# TK90X.net
KiCad netlist of a schematic drawn in EAGLE
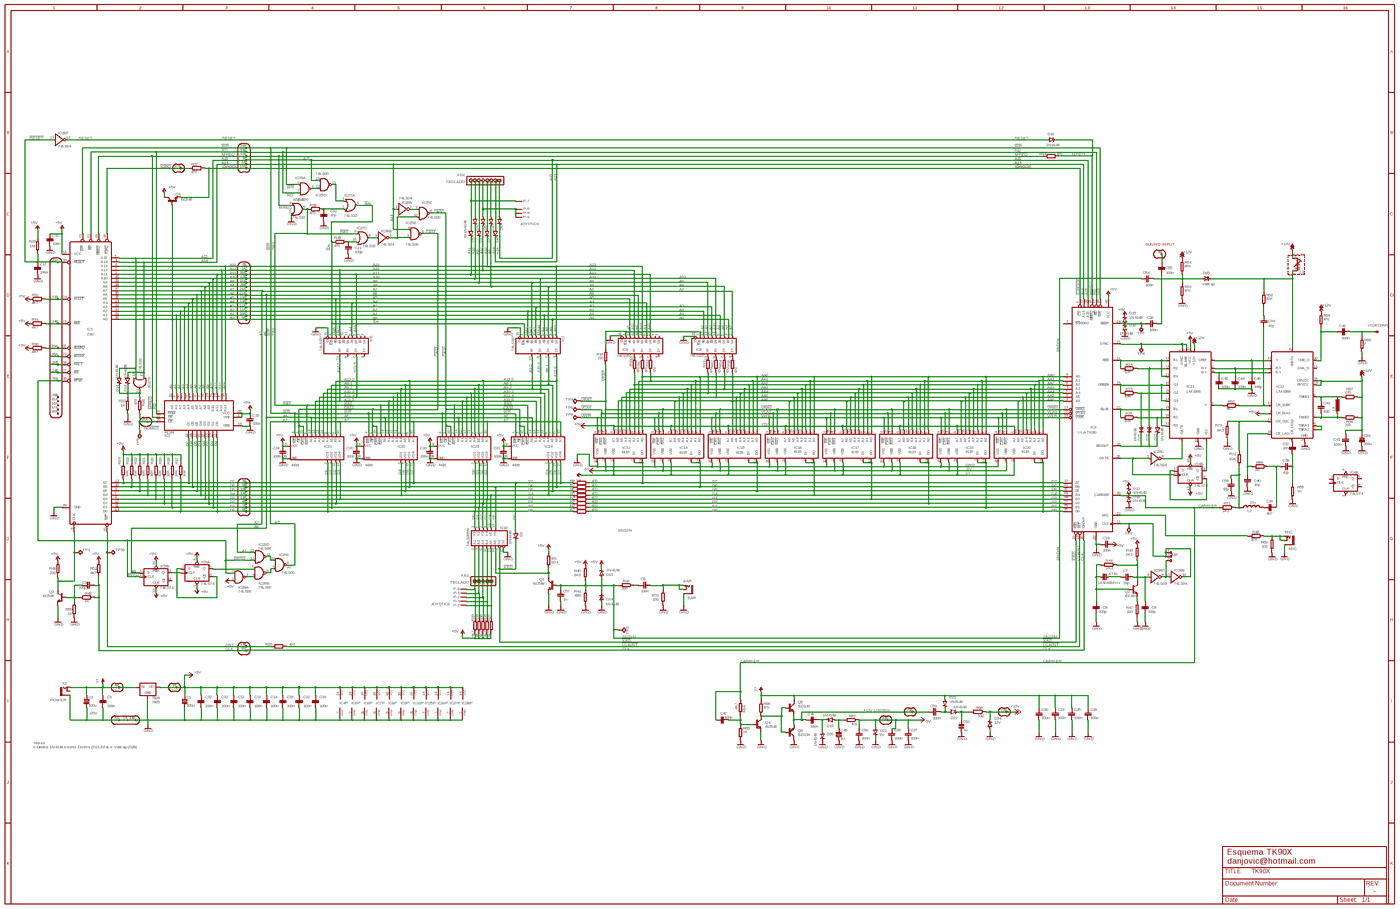
[diagram p0: schematic, sheet 1, overview]
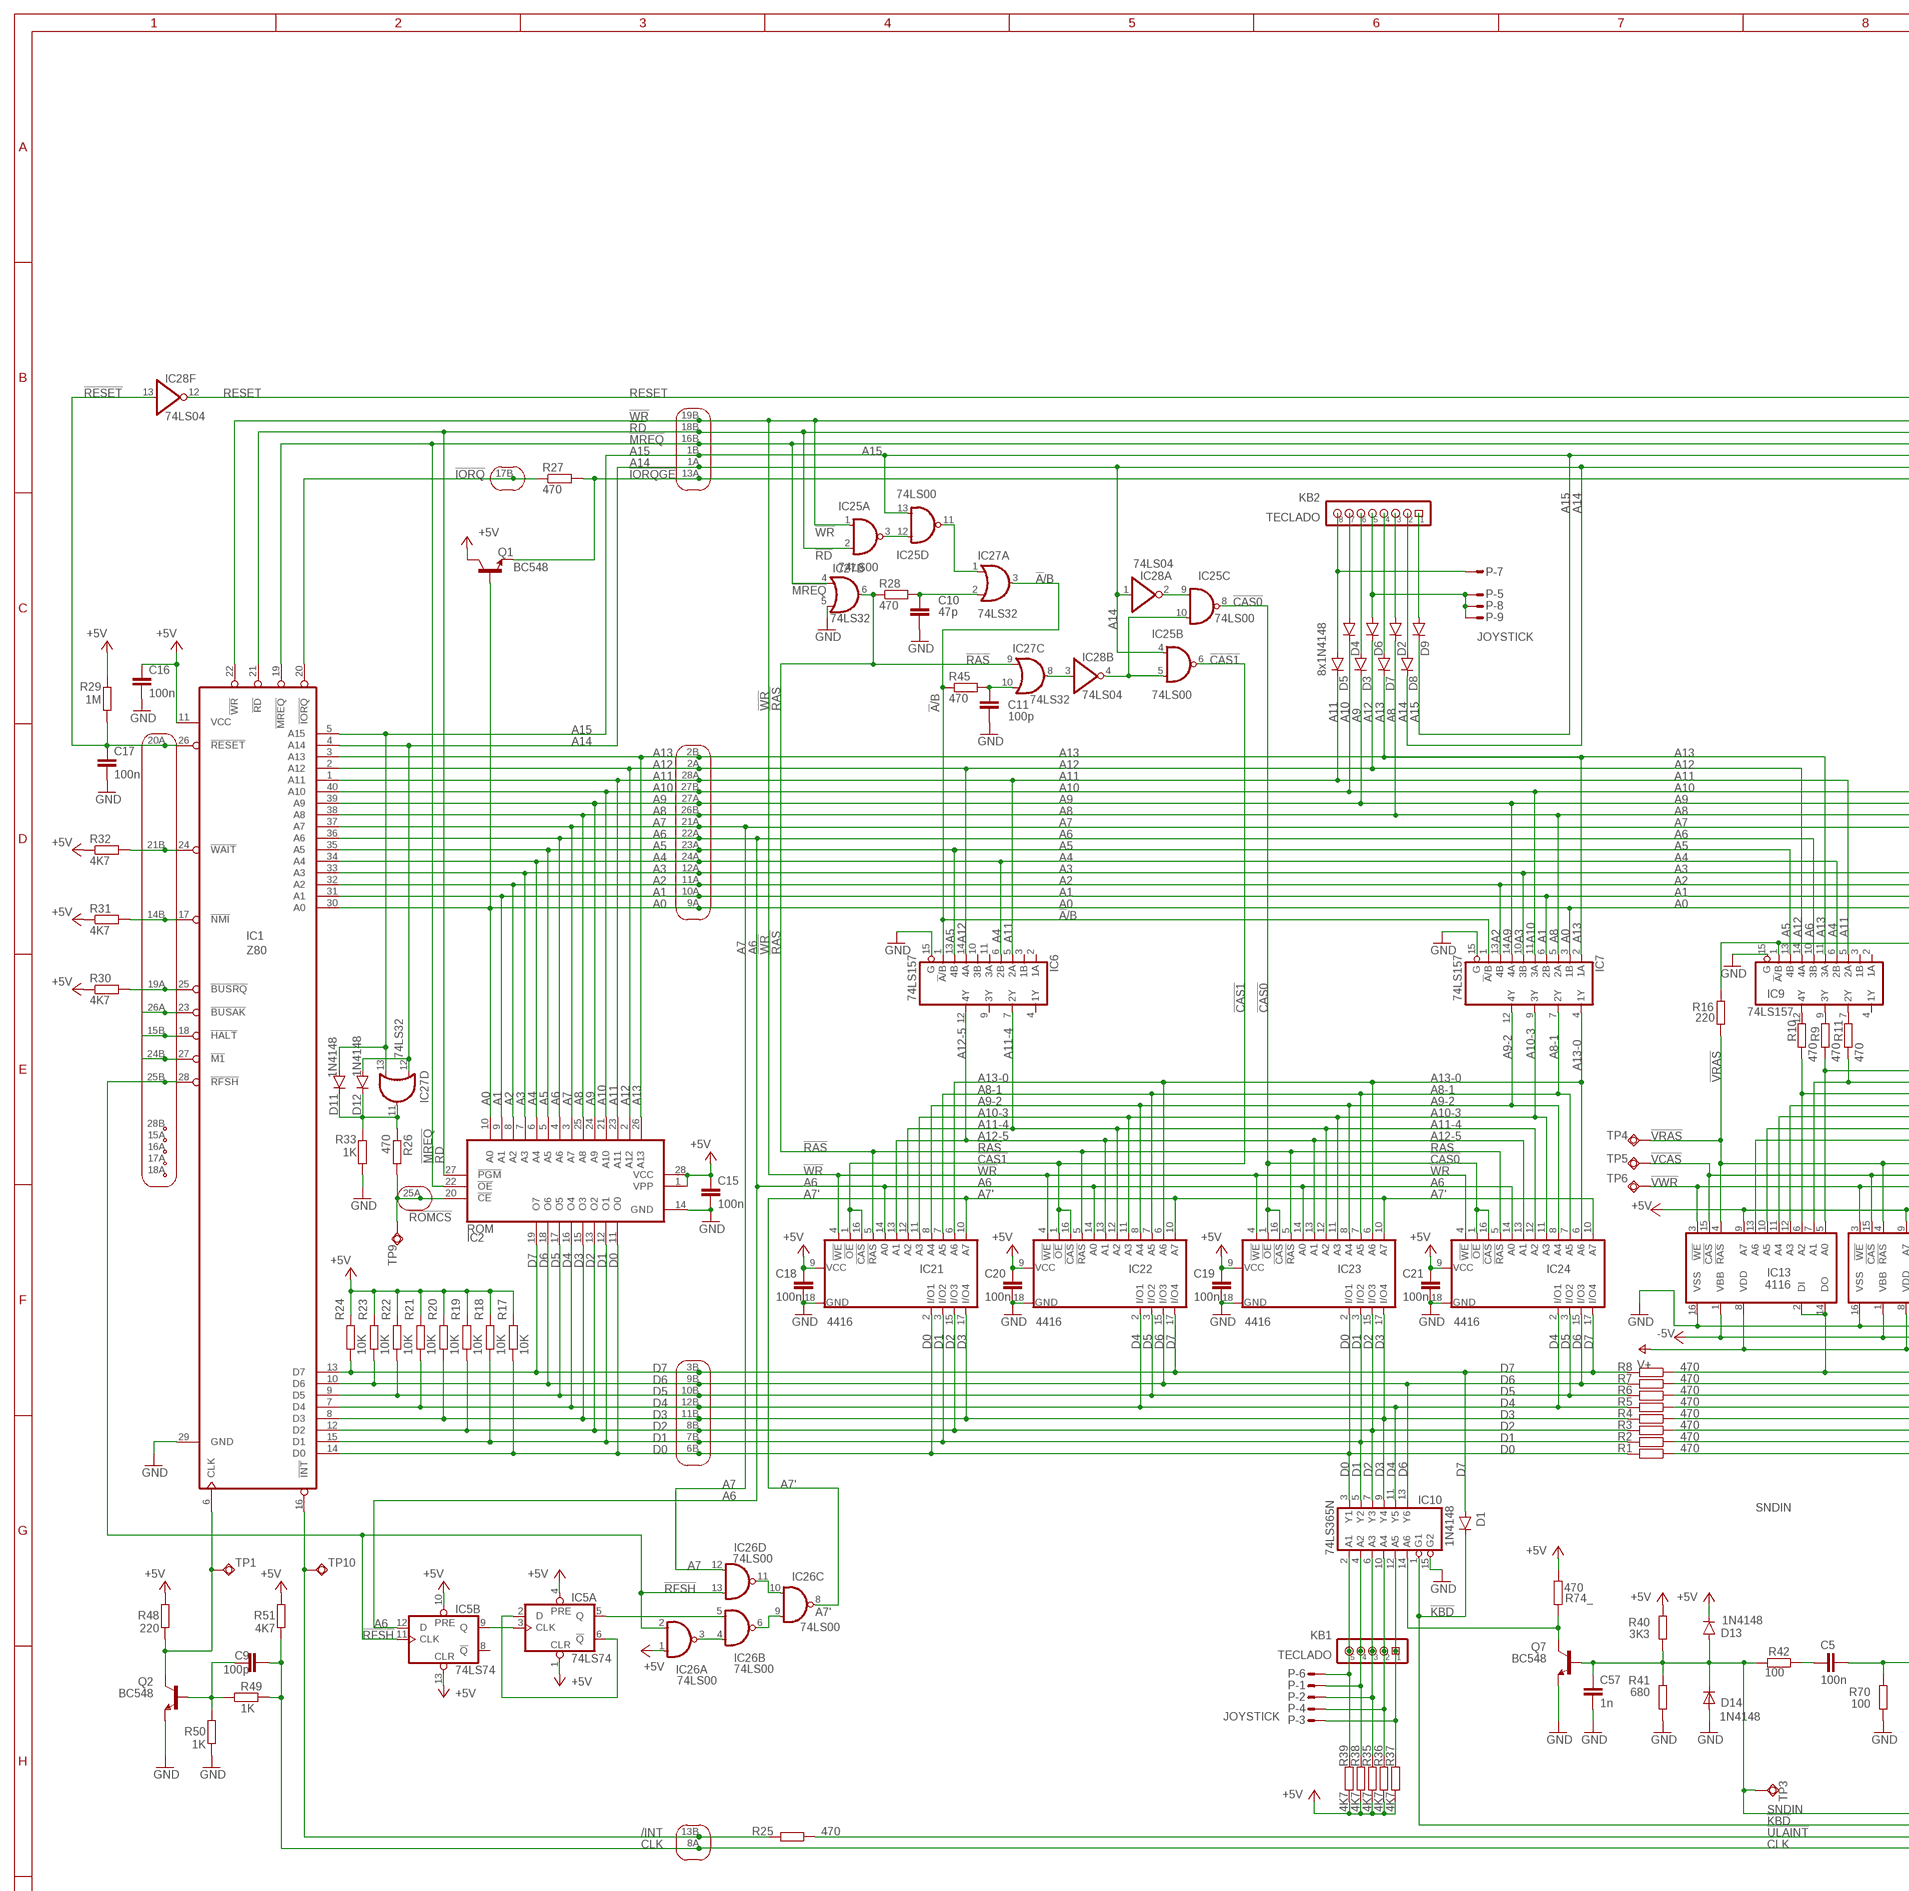
[diagram p1: schematic, sheet 1, part 1 of 4]
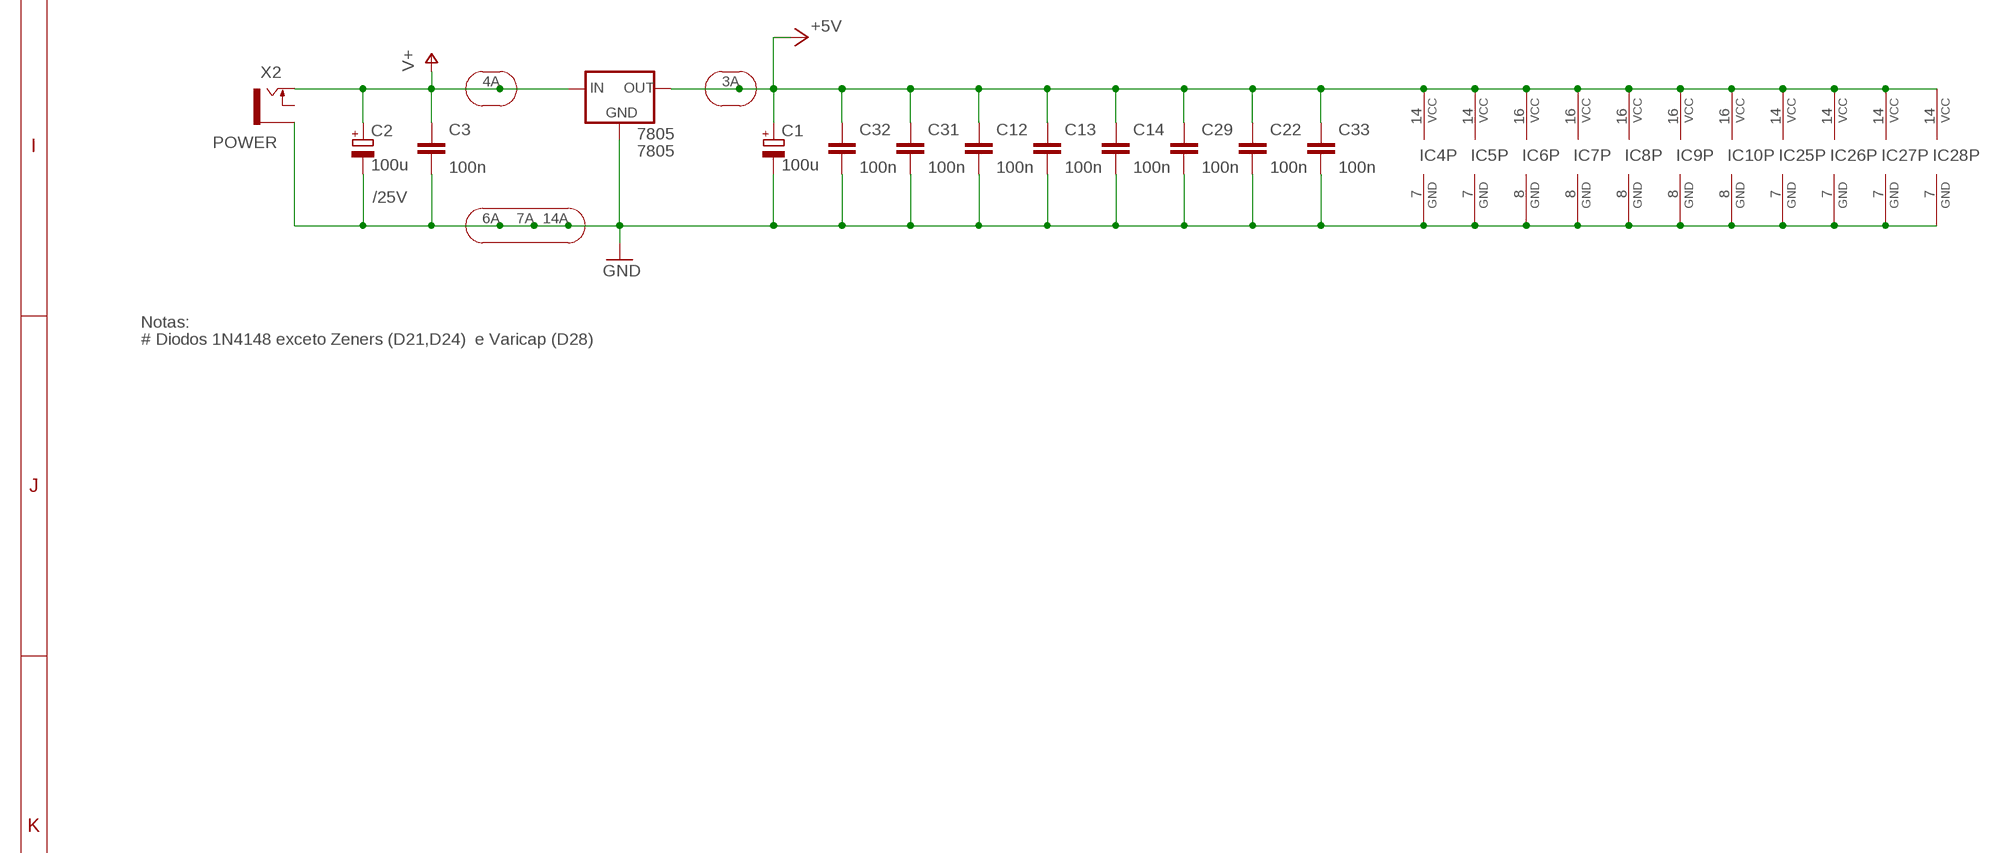
[diagram p2: schematic, sheet 1, part 2 of 4]
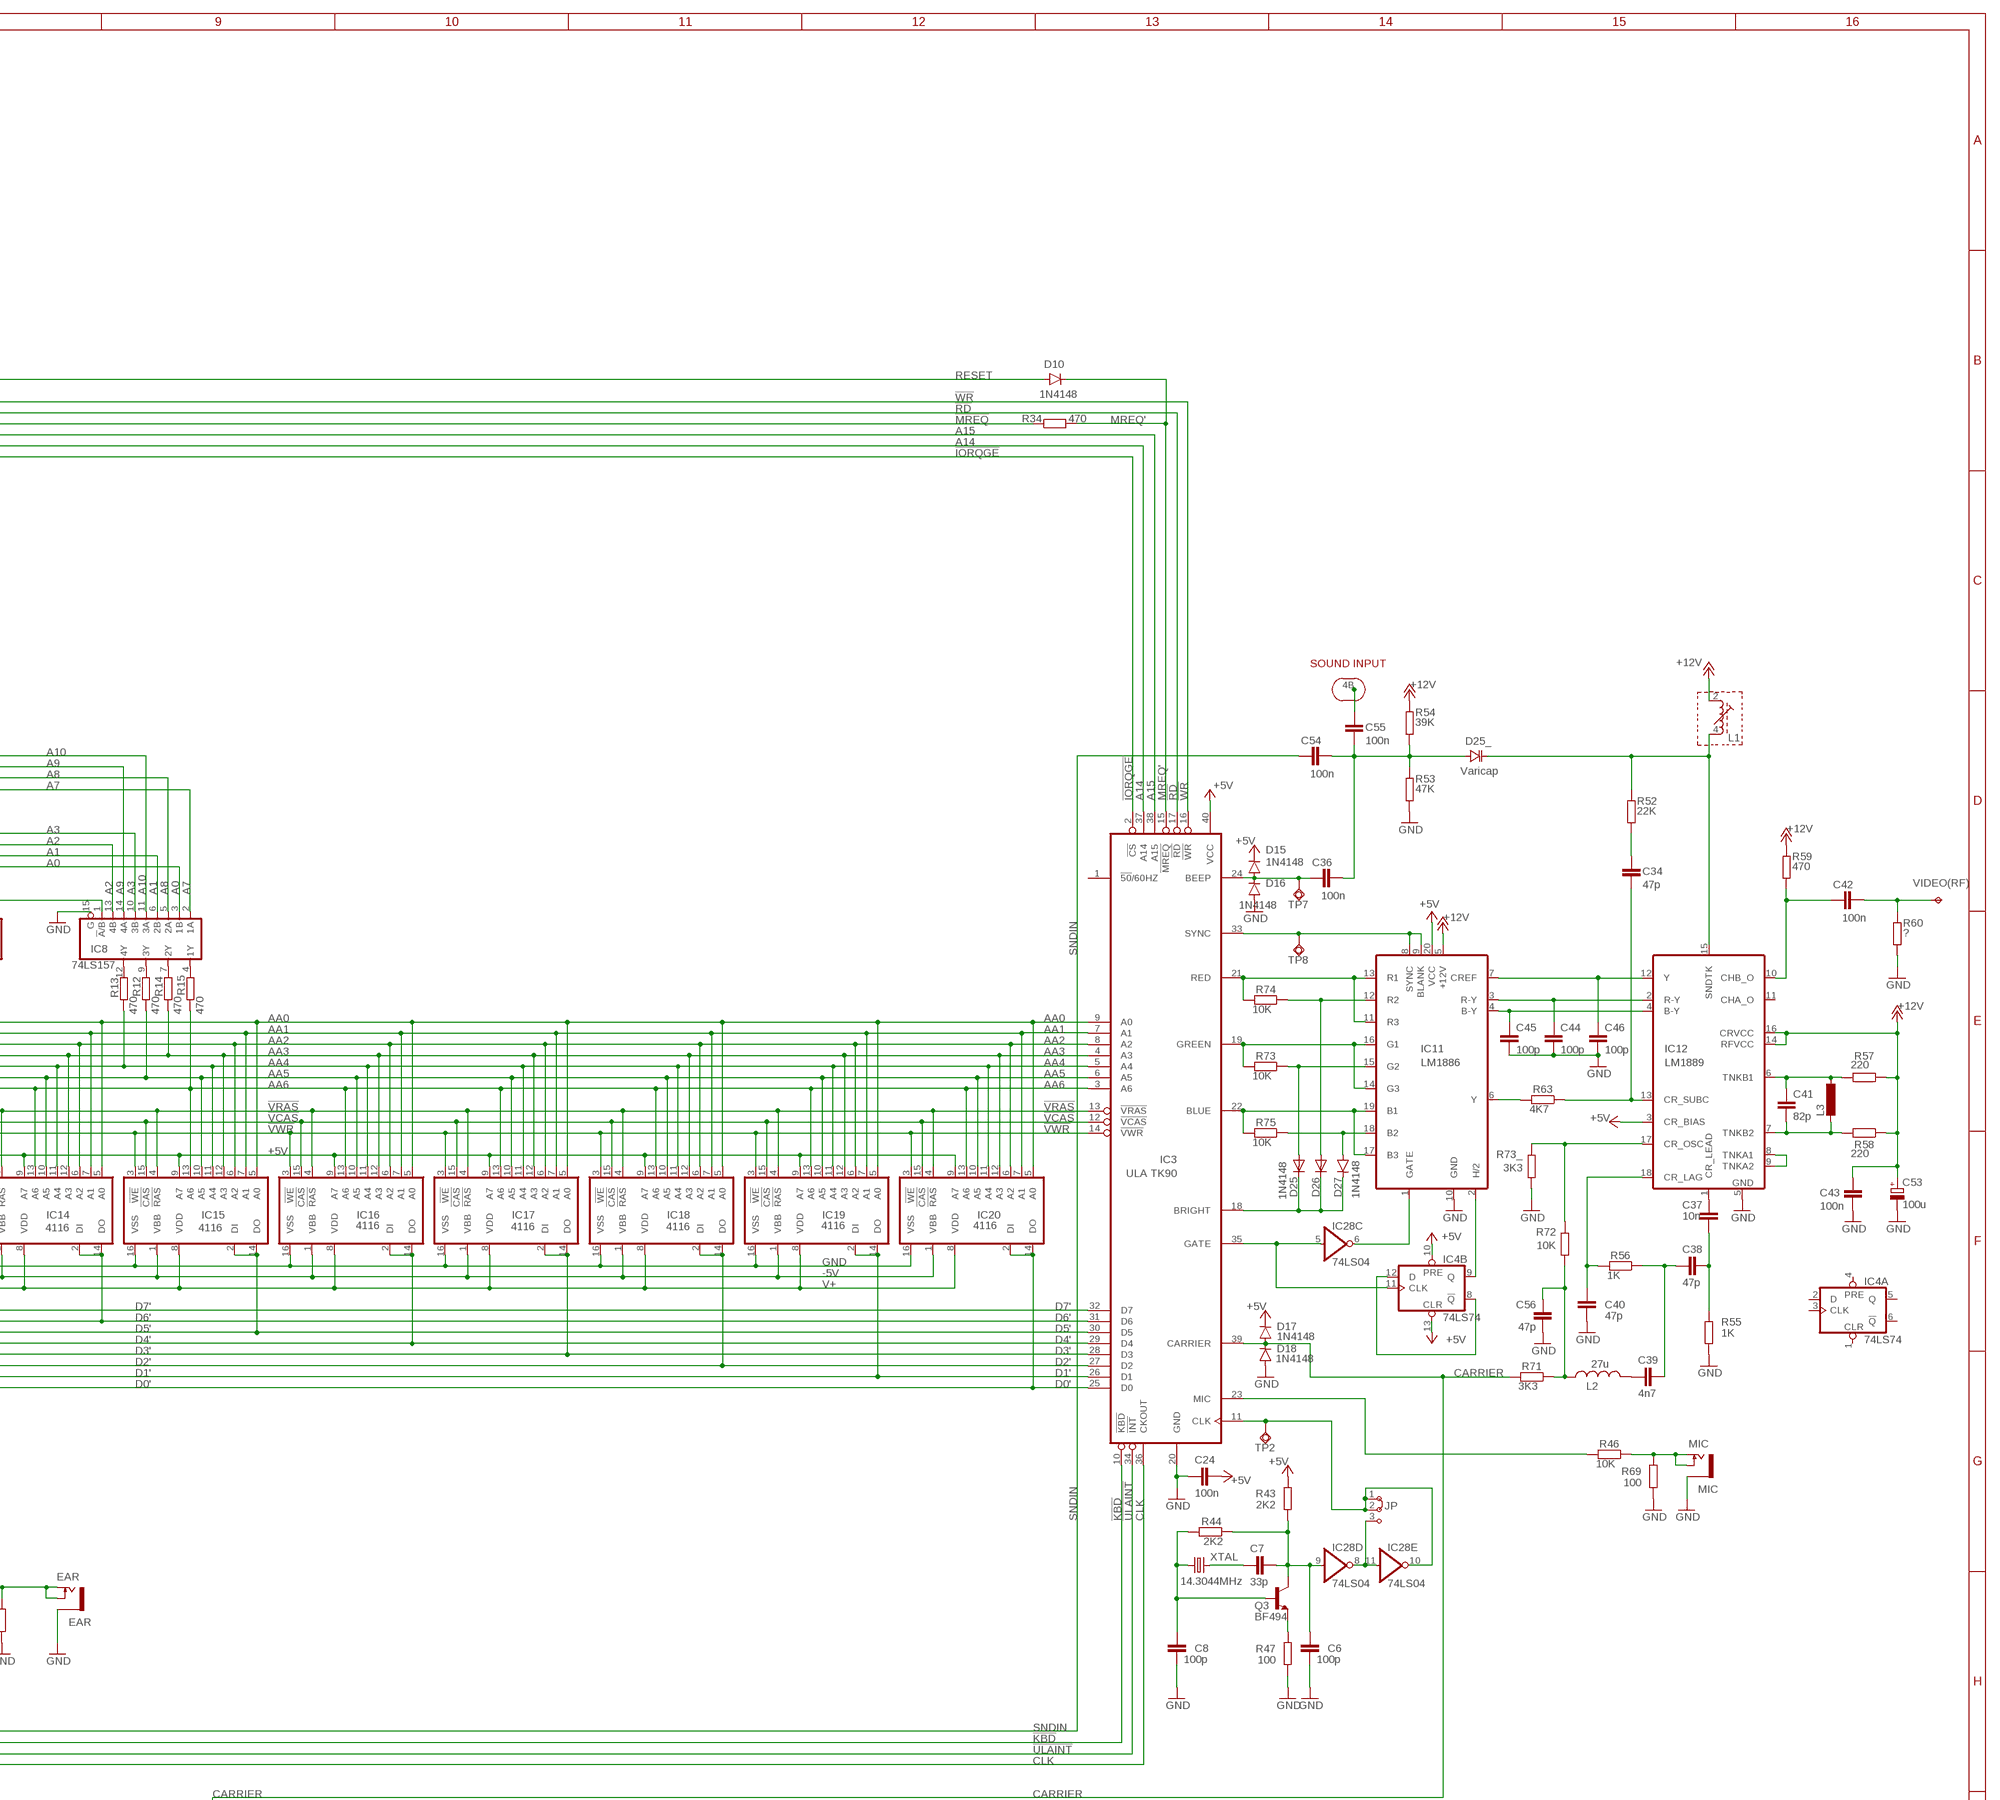
[diagram p3: schematic, sheet 1, part 3 of 4]
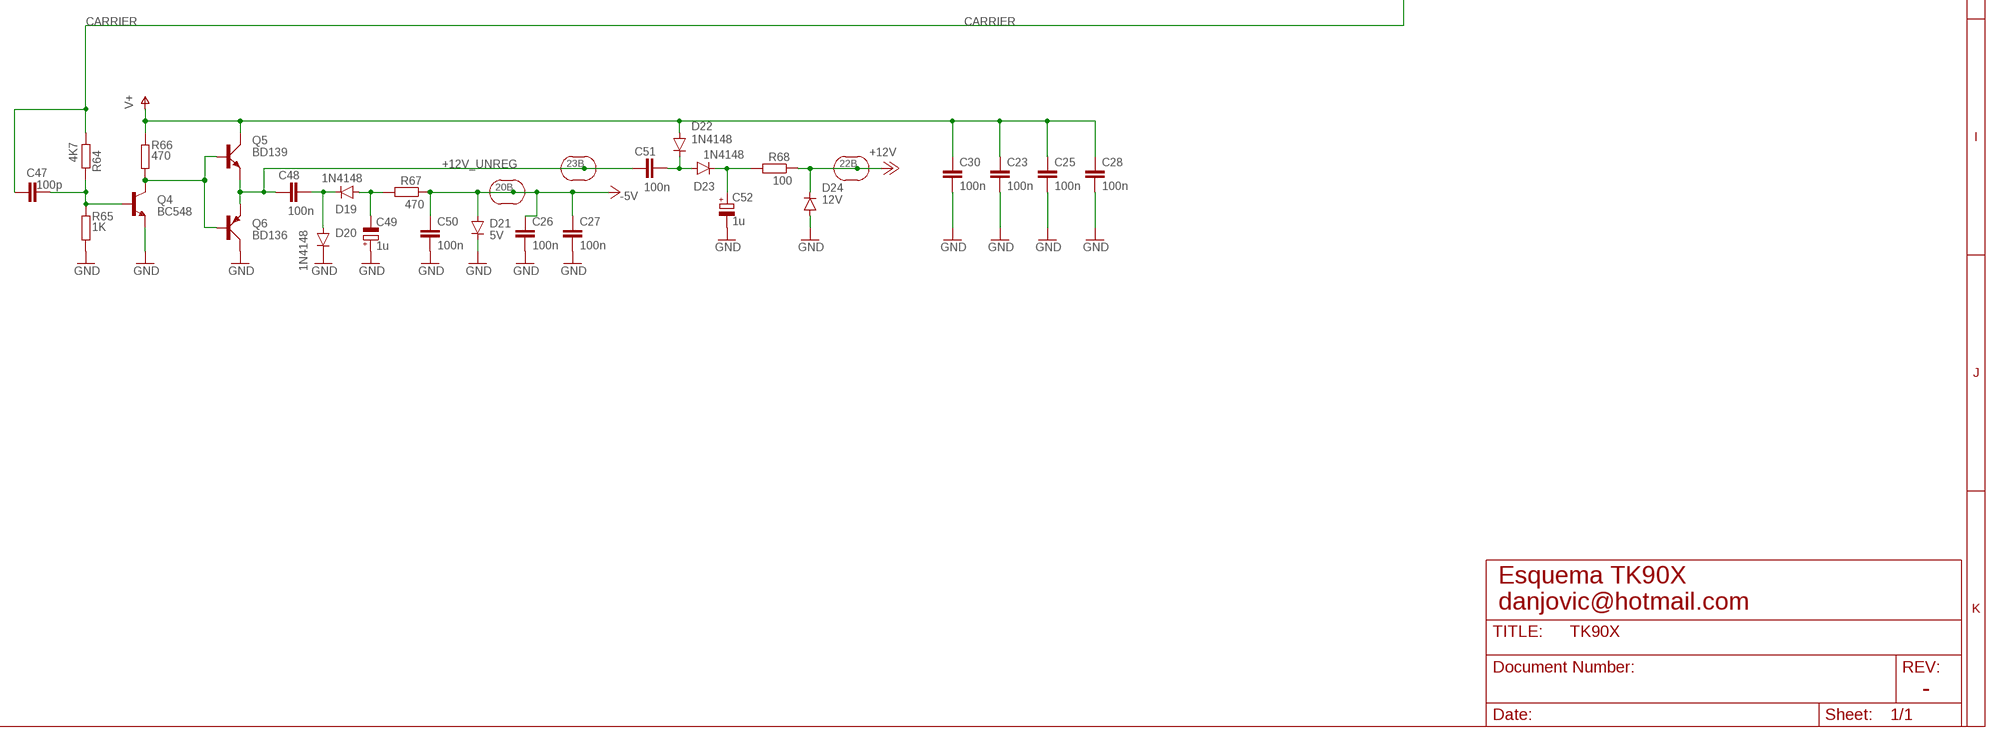
[diagram p4: schematic, sheet 1, part 4 of 4]

(export (version "E")
  (design (tool "Eeschema 10.0.6"))
  (components
    (comp (ref "7805")
      (value "7805")
      (footprint "eagle-import:78XXL")
      (libsource (lib "eagle-import") (part "78XXL"))
    )
    (comp (ref "C1")
      (value "100u")
      (footprint "eagle-import:E5-8,5")
      (libsource (lib "eagle-import") (part "CPOL-EUE5-8.5"))
    )
    (comp (ref "C2")
      (value "100u")
      (footprint "eagle-import:E5-8,5")
      (libsource (lib "eagle-import") (part "CPOL-EUE5-8.5"))
    )
    (comp (ref "C3")
      (value "100n")
      (footprint "eagle-import:C050-024X044")
      (libsource (lib "eagle-import") (part "C-EU050-024X044"))
    )
    (comp (ref "C5")
      (value "100n")
      (footprint "eagle-import:C050-024X044")
      (libsource (lib "eagle-import") (part "C-EU050-024X044"))
    )
    (comp (ref "C6")
      (value "100p")
      (footprint "eagle-import:C050-024X044")
      (libsource (lib "eagle-import") (part "C-EU050-024X044"))
    )
    (comp (ref "C7")
      (value "33p")
      (footprint "eagle-import:C050-024X044")
      (libsource (lib "eagle-import") (part "C-EU050-024X044"))
    )
    (comp (ref "C8")
      (value "100p")
      (footprint "eagle-import:C050-024X044")
      (libsource (lib "eagle-import") (part "C-EU050-024X044"))
    )
    (comp (ref "C9")
      (value "100p")
      (footprint "eagle-import:C050-024X044")
      (libsource (lib "eagle-import") (part "C-EU050-024X044"))
    )
    (comp (ref "C10")
      (value "47p")
      (footprint "eagle-import:C050-024X044")
      (libsource (lib "eagle-import") (part "C-EU050-024X044"))
    )
    (comp (ref "C11")
      (value "100p")
      (footprint "eagle-import:C050-024X044")
      (libsource (lib "eagle-import") (part "C-EU050-024X044"))
    )
    (comp (ref "C12")
      (value "100n")
      (footprint "eagle-import:C050-024X044")
      (libsource (lib "eagle-import") (part "C-EU050-024X044"))
    )
    (comp (ref "C13")
      (value "100n")
      (footprint "eagle-import:C050-024X044")
      (libsource (lib "eagle-import") (part "C-EU050-024X044"))
    )
    (comp (ref "C14")
      (value "100n")
      (footprint "eagle-import:C050-024X044")
      (libsource (lib "eagle-import") (part "C-EU050-024X044"))
    )
    (comp (ref "C15")
      (value "100n")
      (footprint "eagle-import:C050-024X044")
      (libsource (lib "eagle-import") (part "C-EU050-024X044"))
    )
    (comp (ref "C16")
      (value "100n")
      (footprint "eagle-import:C050-024X044")
      (libsource (lib "eagle-import") (part "C-EU050-024X044"))
    )
    (comp (ref "C17")
      (value "100n")
      (footprint "eagle-import:C050-024X044")
      (libsource (lib "eagle-import") (part "C-EU050-024X044"))
    )
    (comp (ref "C18")
      (value "100n")
      (footprint "eagle-import:C050-024X044")
      (libsource (lib "eagle-import") (part "C-EU050-024X044"))
    )
    (comp (ref "C19")
      (value "100n")
      (footprint "eagle-import:C050-024X044")
      (libsource (lib "eagle-import") (part "C-EU050-024X044"))
    )
    (comp (ref "C20")
      (value "100n")
      (footprint "eagle-import:C050-024X044")
      (libsource (lib "eagle-import") (part "C-EU050-024X044"))
    )
    (comp (ref "C21")
      (value "100n")
      (footprint "eagle-import:C050-024X044")
      (libsource (lib "eagle-import") (part "C-EU050-024X044"))
    )
    (comp (ref "C22")
      (value "100n")
      (footprint "eagle-import:C050-024X044")
      (libsource (lib "eagle-import") (part "C-EU050-024X044"))
    )
    (comp (ref "C23")
      (value "100n")
      (footprint "eagle-import:C050-024X044")
      (libsource (lib "eagle-import") (part "C-EU050-024X044"))
    )
    (comp (ref "C24")
      (value "100n")
      (footprint "eagle-import:C050-024X044")
      (libsource (lib "eagle-import") (part "C-EU050-024X044"))
    )
    (comp (ref "C25")
      (value "100n")
      (footprint "eagle-import:C050-024X044")
      (libsource (lib "eagle-import") (part "C-EU050-024X044"))
    )
    (comp (ref "C26")
      (value "100n")
      (footprint "eagle-import:C050-024X044")
      (libsource (lib "eagle-import") (part "C-EU050-024X044"))
    )
    (comp (ref "C27")
      (value "100n")
      (footprint "eagle-import:C050-024X044")
      (libsource (lib "eagle-import") (part "C-EU050-024X044"))
    )
    (comp (ref "C28")
      (value "100n")
      (footprint "eagle-import:C050-024X044")
      (libsource (lib "eagle-import") (part "C-EU050-024X044"))
    )
    (comp (ref "C29")
      (value "100n")
      (footprint "eagle-import:C050-024X044")
      (libsource (lib "eagle-import") (part "C-EU050-024X044"))
    )
    (comp (ref "C30")
      (value "100n")
      (footprint "eagle-import:C050-024X044")
      (libsource (lib "eagle-import") (part "C-EU050-024X044"))
    )
    (comp (ref "C31")
      (value "100n")
      (footprint "eagle-import:C050-024X044")
      (libsource (lib "eagle-import") (part "C-EU050-024X044"))
    )
    (comp (ref "C32")
      (value "100n")
      (footprint "eagle-import:C050-024X044")
      (libsource (lib "eagle-import") (part "C-EU050-024X044"))
    )
    (comp (ref "C33")
      (value "100n")
      (footprint "eagle-import:C050-024X044")
      (libsource (lib "eagle-import") (part "C-EU050-024X044"))
    )
    (comp (ref "C34")
      (value "47p")
      (footprint "eagle-import:C050-024X044")
      (libsource (lib "eagle-import") (part "C-EU050-024X044"))
    )
    (comp (ref "C36")
      (value "100n")
      (footprint "eagle-import:C050-024X044")
      (libsource (lib "eagle-import") (part "C-EU050-024X044"))
    )
    (comp (ref "C37")
      (value "10n")
      (footprint "eagle-import:C050-024X044")
      (libsource (lib "eagle-import") (part "C-EU050-024X044"))
    )
    (comp (ref "C38")
      (value "47p")
      (footprint "eagle-import:C050-024X044")
      (libsource (lib "eagle-import") (part "C-EU050-024X044"))
    )
    (comp (ref "C39")
      (value "4n7")
      (footprint "eagle-import:C050-024X044")
      (libsource (lib "eagle-import") (part "C-EU050-024X044"))
    )
    (comp (ref "C40")
      (value "47p")
      (footprint "eagle-import:C050-024X044")
      (libsource (lib "eagle-import") (part "C-EU050-024X044"))
    )
    (comp (ref "C41")
      (value "82p")
      (footprint "eagle-import:C050-024X044")
      (libsource (lib "eagle-import") (part "C-EU050-024X044"))
    )
    (comp (ref "C42")
      (value "100n")
      (footprint "eagle-import:C050-024X044")
      (libsource (lib "eagle-import") (part "C-EU050-024X044"))
    )
    (comp (ref "C43")
      (value "100n")
      (footprint "eagle-import:C050-024X044")
      (libsource (lib "eagle-import") (part "C-EU050-024X044"))
    )
    (comp (ref "C44")
      (value "100p")
      (footprint "eagle-import:C050-024X044")
      (libsource (lib "eagle-import") (part "C-EU050-024X044"))
    )
    (comp (ref "C45")
      (value "100p")
      (footprint "eagle-import:C050-024X044")
      (libsource (lib "eagle-import") (part "C-EU050-024X044"))
    )
    (comp (ref "C46")
      (value "100p")
      (footprint "eagle-import:C050-024X044")
      (libsource (lib "eagle-import") (part "C-EU050-024X044"))
    )
    (comp (ref "C47")
      (value "100p")
      (footprint "eagle-import:C050-024X044")
      (libsource (lib "eagle-import") (part "C-EU050-024X044"))
    )
    (comp (ref "C48")
      (value "100n")
      (footprint "eagle-import:C050-024X044")
      (libsource (lib "eagle-import") (part "C-EU050-024X044"))
    )
    (comp (ref "C49")
      (value "1u")
      (footprint "eagle-import:E2-4")
      (libsource (lib "eagle-import") (part "CPOL-EUE2-4"))
    )
    (comp (ref "C50")
      (value "100n")
      (footprint "eagle-import:C050-024X044")
      (libsource (lib "eagle-import") (part "C-EU050-024X044"))
    )
    (comp (ref "C51")
      (value "100n")
      (footprint "eagle-import:C050-024X044")
      (libsource (lib "eagle-import") (part "C-EU050-024X044"))
    )
    (comp (ref "C52")
      (value "1u")
      (footprint "eagle-import:E2-5")
      (libsource (lib "eagle-import") (part "CPOL-EUE2-5"))
    )
    (comp (ref "C53")
      (value "100u")
      (footprint "eagle-import:E5-4")
      (libsource (lib "eagle-import") (part "CPOL-EUE5-4"))
    )
    (comp (ref "C54")
      (value "100n")
      (footprint "eagle-import:C050-024X044")
      (libsource (lib "eagle-import") (part "C-EU050-024X044"))
    )
    (comp (ref "C55")
      (value "100n")
      (footprint "eagle-import:C050-024X044")
      (libsource (lib "eagle-import") (part "C-EU050-024X044"))
    )
    (comp (ref "C56")
      (value "47p")
      (footprint "eagle-import:C050-024X044")
      (libsource (lib "eagle-import") (part "C-EU050-024X044"))
    )
    (comp (ref "C57")
      (value "1n")
      (footprint "eagle-import:C050-024X044")
      (libsource (lib "eagle-import") (part "C-EU050-024X044"))
    )
    (comp (ref "D1")
      (value "1N4148")
      (footprint "eagle-import:DO35-12")
      (libsource (lib "eagle-import") (part "DDO35-12"))
    )
    (comp (ref "D2")
      (value "1N4148")
      (footprint "eagle-import:DO35-12")
      (libsource (lib "eagle-import") (part "DDO35-12"))
    )
    (comp (ref "D3")
      (value "1N4148")
      (footprint "eagle-import:DO35-12")
      (libsource (lib "eagle-import") (part "DDO35-12"))
    )
    (comp (ref "D4")
      (value "1N4148")
      (footprint "eagle-import:DO35-12")
      (libsource (lib "eagle-import") (part "DDO35-12"))
    )
    (comp (ref "D5")
      (value "1N4148")
      (footprint "eagle-import:DO35-12")
      (libsource (lib "eagle-import") (part "DDO35-12"))
    )
    (comp (ref "D6")
      (value "1N4148")
      (footprint "eagle-import:DO35-12")
      (libsource (lib "eagle-import") (part "DDO35-12"))
    )
    (comp (ref "D7")
      (value "1N4148")
      (footprint "eagle-import:DO35-12")
      (libsource (lib "eagle-import") (part "DDO35-12"))
    )
    (comp (ref "D8")
      (value "1N4148")
      (footprint "eagle-import:DO35-12")
      (libsource (lib "eagle-import") (part "DDO35-12"))
    )
    (comp (ref "D9")
      (value "1N4148")
      (footprint "eagle-import:DO35-12")
      (libsource (lib "eagle-import") (part "DDO35-12"))
    )
    (comp (ref "D10")
      (value "1N4148")
      (footprint "eagle-import:DO35-12")
      (libsource (lib "eagle-import") (part "DDO35-12"))
    )
    (comp (ref "D11")
      (value "1N4148")
      (footprint "eagle-import:DO35-12")
      (libsource (lib "eagle-import") (part "DDO35-12"))
    )
    (comp (ref "D12")
      (value "1N4148")
      (footprint "eagle-import:DO35-12")
      (libsource (lib "eagle-import") (part "DDO35-12"))
    )
    (comp (ref "D13")
      (value "1N4148")
      (footprint "eagle-import:DO35-12")
      (libsource (lib "eagle-import") (part "DDO35-12"))
    )
    (comp (ref "D14")
      (value "1N4148")
      (footprint "eagle-import:D-5")
      (libsource (lib "eagle-import") (part "DIODE-D-5"))
    )
    (comp (ref "D15")
      (value "1N4148")
      (footprint "eagle-import:DO35-12")
      (libsource (lib "eagle-import") (part "DDO35-12"))
    )
    (comp (ref "D16")
      (value "1N4148")
      (footprint "eagle-import:DO35-12")
      (libsource (lib "eagle-import") (part "DDO35-12"))
    )
    (comp (ref "D17")
      (value "1N4148")
      (footprint "eagle-import:DO35-12")
      (libsource (lib "eagle-import") (part "DDO35-12"))
    )
    (comp (ref "D18")
      (value "1N4148")
      (footprint "eagle-import:DO35-12")
      (libsource (lib "eagle-import") (part "DDO35-12"))
    )
    (comp (ref "D19")
      (value "1N4148")
      (footprint "eagle-import:DO35-12")
      (libsource (lib "eagle-import") (part "DDO35-12"))
    )
    (comp (ref "D20")
      (value "1N4148")
      (footprint "eagle-import:DO35-12")
      (libsource (lib "eagle-import") (part "DDO35-12"))
    )
    (comp (ref "D21")
      (value "5V")
      (footprint "eagle-import:DO35-12")
      (libsource (lib "eagle-import") (part "DDO35-12"))
    )
    (comp (ref "D22")
      (value "1N4148")
      (footprint "eagle-import:DO35-12")
      (libsource (lib "eagle-import") (part "DDO35-12"))
    )
    (comp (ref "D23")
      (value "1N4148")
      (footprint "eagle-import:DO35-12")
      (libsource (lib "eagle-import") (part "DDO35-12"))
    )
    (comp (ref "D24")
      (value "12V")
      (footprint "eagle-import:DO35-12")
      (libsource (lib "eagle-import") (part "DDO35-12"))
    )
    (comp (ref "D25")
      (value "1N4148")
      (footprint "eagle-import:D-5")
      (libsource (lib "eagle-import") (part "DIODE-D-5"))
    )
    (comp (ref "D25_")
      (value "Varicap")
      (footprint "eagle-import:D200")
      (libsource (lib "eagle-import") (part "VARICAP-200"))
    )
    (comp (ref "D26")
      (value "1N4148")
      (footprint "eagle-import:D-5")
      (libsource (lib "eagle-import") (part "DIODE-D-5"))
    )
    (comp (ref "D27")
      (value "1N4148")
      (footprint "eagle-import:DO35-12")
      (libsource (lib "eagle-import") (part "DDO35-12"))
    )
    (comp (ref "EAR")
      (value "EAR")
      (footprint "eagle-import:MONO")
      (libsource (lib "eagle-import") (part "JACK?-MONO"))
    )
    (comp (ref "IC1")
      (value "Z80")
      (footprint "eagle-import:DIL40")
      (libsource (lib "eagle-import") (part "Z80CPU"))
    )
    (comp (ref "IC2")
      (value "ROM")
      (footprint "eagle-import:DIL28")
      (libsource (lib "eagle-import") (part "25128"))
    )
    (comp (ref "IC3")
      (value "ULA TK90")
      (footprint "eagle-import:DIL40")
      (libsource (lib "eagle-import") (part "ULA-TK90"))
    )
    (comp (ref "IC4")
      (value "74LS74")
      (footprint "eagle-import:DIL14")
      (libsource (lib "eagle-import") (part "7474NLS"))
    )
    (comp (ref "IC5")
      (value "74LS74")
      (footprint "eagle-import:DIL14")
      (libsource (lib "eagle-import") (part "7474NLS"))
    )
    (comp (ref "IC6")
      (value "74LS157")
      (footprint "eagle-import:DIL16")
      (libsource (lib "eagle-import") (part "74157NS"))
    )
    (comp (ref "IC7")
      (value "74LS157")
      (footprint "eagle-import:DIL16")
      (libsource (lib "eagle-import") (part "74157NS"))
    )
    (comp (ref "IC8")
      (value "74LS157")
      (footprint "eagle-import:DIL16")
      (libsource (lib "eagle-import") (part "74157NS"))
    )
    (comp (ref "IC9")
      (value "74LS157")
      (footprint "eagle-import:DIL16")
      (libsource (lib "eagle-import") (part "74157NS"))
    )
    (comp (ref "IC10")
      (value "74LS365N")
      (footprint "eagle-import:DIL16")
      (libsource (lib "eagle-import") (part "74365NLS"))
    )
    (comp (ref "IC11")
      (value "LM1886")
      (footprint "eagle-import:DIL20")
      (libsource (lib "eagle-import") (part "LM1886N"))
    )
    (comp (ref "IC12")
      (value "LM1889")
      (footprint "eagle-import:DIL18")
      (libsource (lib "eagle-import") (part "LM1889"))
    )
    (comp (ref "IC13")
      (value "4116")
      (footprint "eagle-import:DIL16")
      (libsource (lib "eagle-import") (part "MK4516"))
    )
    (comp (ref "IC14")
      (value "4116")
      (footprint "eagle-import:DIL16")
      (libsource (lib "eagle-import") (part "MK4516"))
    )
    (comp (ref "IC15")
      (value "4116")
      (footprint "eagle-import:DIL16")
      (libsource (lib "eagle-import") (part "MK4516"))
    )
    (comp (ref "IC16")
      (value "4116")
      (footprint "eagle-import:DIL16")
      (libsource (lib "eagle-import") (part "MK4516"))
    )
    (comp (ref "IC17")
      (value "4116")
      (footprint "eagle-import:DIL16")
      (libsource (lib "eagle-import") (part "MK4516"))
    )
    (comp (ref "IC18")
      (value "4116")
      (footprint "eagle-import:DIL16")
      (libsource (lib "eagle-import") (part "MK4516"))
    )
    (comp (ref "IC19")
      (value "4116")
      (footprint "eagle-import:DIL16")
      (libsource (lib "eagle-import") (part "MK4516"))
    )
    (comp (ref "IC20")
      (value "4116")
      (footprint "eagle-import:DIL16")
      (libsource (lib "eagle-import") (part "MK4516"))
    )
    (comp (ref "IC21")
      (value "4416")
      (footprint "eagle-import:DIL18")
      (libsource (lib "eagle-import") (part "4416"))
    )
    (comp (ref "IC22")
      (value "4416")
      (footprint "eagle-import:DIL18")
      (libsource (lib "eagle-import") (part "4416"))
    )
    (comp (ref "IC23")
      (value "4416")
      (footprint "eagle-import:DIL18")
      (libsource (lib "eagle-import") (part "4416"))
    )
    (comp (ref "IC24")
      (value "4416")
      (footprint "eagle-import:DIL18")
      (libsource (lib "eagle-import") (part "4416"))
    )
    (comp (ref "IC25")
      (value "74LS00")
      (footprint "eagle-import:DIL14")
      (libsource (lib "eagle-import") (part "7400NLS"))
    )
    (comp (ref "IC26")
      (value "74LS00")
      (footprint "eagle-import:DIL14")
      (libsource (lib "eagle-import") (part "7400NLS"))
    )
    (comp (ref "IC27")
      (value "74LS32")
      (footprint "eagle-import:DIL14")
      (libsource (lib "eagle-import") (part "7432NLS"))
    )
    (comp (ref "IC28")
      (value "74LS04")
      (footprint "eagle-import:DIL14")
      (libsource (lib "eagle-import") (part "7404NLS"))
    )
    (comp (ref "JP")
      (value "J2X1MM")
      (footprint "eagle-import:03C")
      (libsource (lib "eagle-import") (part "J2X1MM"))
    )
    (comp (ref "KB1")
      (value "TECLADO")
      (footprint "eagle-import:FE05-1")
      (libsource (lib "eagle-import") (part "CON-TECL-5"))
    )
    (comp (ref "KB2")
      (value "TECLADO")
      (footprint "eagle-import:FE08")
      (libsource (lib "eagle-import") (part "CON-TECL-8"))
    )
    (comp (ref "L1")
      (value "COIL")
      (footprint "eagle-import:COIL")
      (libsource (lib "eagle-import") (part "COIL"))
    )
    (comp (ref "L2")
      (value "27u")
      (footprint "eagle-import:0207_7")
      (libsource (lib "eagle-import") (part "L-US0207/7"))
    )
    (comp (ref "L3")
      (value "L-EU0204/5")
      (footprint "eagle-import:0204_5")
      (libsource (lib "eagle-import") (part "L-EU0204/5"))
    )
    (comp (ref "MIC")
      (value "MIC")
      (footprint "eagle-import:MONO")
      (libsource (lib "eagle-import") (part "JACK?-MONO"))
    )
    (comp (ref "P")
      (value "JOYSTICK")
      (footprint "eagle-import:177-009-MALE")
      (libsource (lib "eagle-import") (part "M09?S.590"))
    )
    (comp (ref "Q1")
      (value "BC548")
      (footprint "eagle-import:TO92L")
      (libsource (lib "eagle-import") (part "-NPN-TO92L"))
    )
    (comp (ref "Q2")
      (value "BC548")
      (footprint "eagle-import:TO92L")
      (libsource (lib "eagle-import") (part "-NPN-TO92L"))
    )
    (comp (ref "Q3")
      (value "BF494")
      (footprint "eagle-import:TO92-CEB")
      (libsource (lib "eagle-import") (part "BF494"))
    )
    (comp (ref "Q4")
      (value "BC548")
      (footprint "eagle-import:TO92L")
      (libsource (lib "eagle-import") (part "-NPN-TO92L"))
    )
    (comp (ref "Q5")
      (value "BD139")
      (footprint "eagle-import:TO126AV")
      (libsource (lib "eagle-import") (part "BD139"))
    )
    (comp (ref "Q6")
      (value "BD136")
      (footprint "eagle-import:TO126AV")
      (libsource (lib "eagle-import") (part "BD140"))
    )
    (comp (ref "Q7")
      (value "BC548")
      (footprint "eagle-import:TO92L")
      (libsource (lib "eagle-import") (part "-NPN-TO92L"))
    )
    (comp (ref "R1")
      (value "470")
      (footprint "eagle-import:0207_12")
      (libsource (lib "eagle-import") (part "R-EU_0207/12"))
    )
    (comp (ref "R2")
      (value "470")
      (footprint "eagle-import:0207_12")
      (libsource (lib "eagle-import") (part "R-EU_0207/12"))
    )
    (comp (ref "R3")
      (value "470")
      (footprint "eagle-import:0207_12")
      (libsource (lib "eagle-import") (part "R-EU_0207/12"))
    )
    (comp (ref "R4")
      (value "470")
      (footprint "eagle-import:0207_12")
      (libsource (lib "eagle-import") (part "R-EU_0207/12"))
    )
    (comp (ref "R5")
      (value "470")
      (footprint "eagle-import:0207_12")
      (libsource (lib "eagle-import") (part "R-EU_0207/12"))
    )
    (comp (ref "R6")
      (value "470")
      (footprint "eagle-import:0207_12")
      (libsource (lib "eagle-import") (part "R-EU_0207/12"))
    )
    (comp (ref "R7")
      (value "470")
      (footprint "eagle-import:0207_12")
      (libsource (lib "eagle-import") (part "R-EU_0207/12"))
    )
    (comp (ref "R8")
      (value "470")
      (footprint "eagle-import:0207_12")
      (libsource (lib "eagle-import") (part "R-EU_0207/12"))
    )
    (comp (ref "R9")
      (value "470")
      (footprint "eagle-import:0207_12")
      (libsource (lib "eagle-import") (part "R-EU_0207/12"))
    )
    (comp (ref "R10")
      (value "470")
      (footprint "eagle-import:0207_12")
      (libsource (lib "eagle-import") (part "R-EU_0207/12"))
    )
    (comp (ref "R11")
      (value "470")
      (footprint "eagle-import:0207_12")
      (libsource (lib "eagle-import") (part "R-EU_0207/12"))
    )
    (comp (ref "R12")
      (value "470")
      (footprint "eagle-import:0207_12")
      (libsource (lib "eagle-import") (part "R-EU_0207/12"))
    )
    (comp (ref "R13")
      (value "470")
      (footprint "eagle-import:0207_12")
      (libsource (lib "eagle-import") (part "R-EU_0207/12"))
    )
    (comp (ref "R14")
      (value "470")
      (footprint "eagle-import:0207_12")
      (libsource (lib "eagle-import") (part "R-EU_0207/12"))
    )
    (comp (ref "R15")
      (value "470")
      (footprint "eagle-import:0207_12")
      (libsource (lib "eagle-import") (part "R-EU_0207/12"))
    )
    (comp (ref "R16")
      (value "220")
      (footprint "eagle-import:0207_12")
      (libsource (lib "eagle-import") (part "R-EU_0207/12"))
    )
    (comp (ref "R17")
      (value "10K")
      (footprint "eagle-import:0207_12")
      (libsource (lib "eagle-import") (part "R-EU_0207/12"))
    )
    (comp (ref "R18")
      (value "10K")
      (footprint "eagle-import:0207_12")
      (libsource (lib "eagle-import") (part "R-EU_0207/12"))
    )
    (comp (ref "R19")
      (value "10K")
      (footprint "eagle-import:0207_12")
      (libsource (lib "eagle-import") (part "R-EU_0207/12"))
    )
    (comp (ref "R20")
      (value "10K")
      (footprint "eagle-import:0207_12")
      (libsource (lib "eagle-import") (part "R-EU_0207/12"))
    )
    (comp (ref "R21")
      (value "10K")
      (footprint "eagle-import:0207_12")
      (libsource (lib "eagle-import") (part "R-EU_0207/12"))
    )
    (comp (ref "R22")
      (value "10K")
      (footprint "eagle-import:0207_12")
      (libsource (lib "eagle-import") (part "R-EU_0207/12"))
    )
    (comp (ref "R23")
      (value "10K")
      (footprint "eagle-import:0207_12")
      (libsource (lib "eagle-import") (part "R-EU_0207/12"))
    )
    (comp (ref "R24")
      (value "10K")
      (footprint "eagle-import:0207_12")
      (libsource (lib "eagle-import") (part "R-EU_0207/12"))
    )
    (comp (ref "R25")
      (value "470")
      (footprint "eagle-import:0207_12")
      (libsource (lib "eagle-import") (part "R-EU_0207/12"))
    )
    (comp (ref "R26")
      (value "470")
      (footprint "eagle-import:0207_12")
      (libsource (lib "eagle-import") (part "R-EU_0207/12"))
    )
    (comp (ref "R27")
      (value "470")
      (footprint "eagle-import:0207_12")
      (libsource (lib "eagle-import") (part "R-EU_0207/12"))
    )
    (comp (ref "R28")
      (value "470")
      (footprint "eagle-import:0207_12")
      (libsource (lib "eagle-import") (part "R-EU_0207/12"))
    )
    (comp (ref "R29")
      (value "1M")
      (footprint "eagle-import:0207_12")
      (libsource (lib "eagle-import") (part "R-EU_0207/12"))
    )
    (comp (ref "R30")
      (value "4K7")
      (footprint "eagle-import:0207_12")
      (libsource (lib "eagle-import") (part "R-EU_0207/12"))
    )
    (comp (ref "R31")
      (value "4K7")
      (footprint "eagle-import:0207_12")
      (libsource (lib "eagle-import") (part "R-EU_0207/12"))
    )
    (comp (ref "R32")
      (value "4K7")
      (footprint "eagle-import:0207_12")
      (libsource (lib "eagle-import") (part "R-EU_0207/12"))
    )
    (comp (ref "R33")
      (value "1K")
      (footprint "eagle-import:0207_12")
      (libsource (lib "eagle-import") (part "R-EU_0207/12"))
    )
    (comp (ref "R34")
      (value "470")
      (footprint "eagle-import:0207_12")
      (libsource (lib "eagle-import") (part "R-EU_0207/12"))
    )
    (comp (ref "R35")
      (value "4K7")
      (footprint "eagle-import:0207_12")
      (libsource (lib "eagle-import") (part "R-EU_0207/12"))
    )
    (comp (ref "R36")
      (value "4K7")
      (footprint "eagle-import:0207_12")
      (libsource (lib "eagle-import") (part "R-EU_0207/12"))
    )
    (comp (ref "R37")
      (value "4K7")
      (footprint "eagle-import:0207_12")
      (libsource (lib "eagle-import") (part "R-EU_0207/12"))
    )
    (comp (ref "R38")
      (value "4K7")
      (footprint "eagle-import:0207_12")
      (libsource (lib "eagle-import") (part "R-EU_0207/12"))
    )
    (comp (ref "R39")
      (value "4K7")
      (footprint "eagle-import:0207_12")
      (libsource (lib "eagle-import") (part "R-EU_0207/12"))
    )
    (comp (ref "R40")
      (value "3K3")
      (footprint "eagle-import:0207_12")
      (libsource (lib "eagle-import") (part "R-EU_0207/12"))
    )
    (comp (ref "R41")
      (value "680")
      (footprint "eagle-import:0207_5V")
      (libsource (lib "eagle-import") (part "R-EU_0207/5V"))
    )
    (comp (ref "R42")
      (value "100")
      (footprint "eagle-import:0207_5V")
      (libsource (lib "eagle-import") (part "R-EU_0207/5V"))
    )
    (comp (ref "R43")
      (value "2K2")
      (footprint "eagle-import:0207_12")
      (libsource (lib "eagle-import") (part "R-EU_0207/12"))
    )
    (comp (ref "R44")
      (value "2K2")
      (footprint "eagle-import:0207_12")
      (libsource (lib "eagle-import") (part "R-EU_0207/12"))
    )
    (comp (ref "R45")
      (value "470")
      (footprint "eagle-import:0207_12")
      (libsource (lib "eagle-import") (part "R-EU_0207/12"))
    )
    (comp (ref "R46")
      (value "10K")
      (footprint "eagle-import:0207_12")
      (libsource (lib "eagle-import") (part "R-EU_0207/12"))
    )
    (comp (ref "R47")
      (value "100")
      (footprint "eagle-import:0207_12")
      (libsource (lib "eagle-import") (part "R-EU_0207/12"))
    )
    (comp (ref "R48")
      (value "220")
      (footprint "eagle-import:0207_12")
      (libsource (lib "eagle-import") (part "R-EU_0207/12"))
    )
    (comp (ref "R49")
      (value "1K")
      (footprint "eagle-import:0207_12")
      (libsource (lib "eagle-import") (part "R-EU_0207/12"))
    )
    (comp (ref "R50")
      (value "1K")
      (footprint "eagle-import:0207_12")
      (libsource (lib "eagle-import") (part "R-EU_0207/12"))
    )
    (comp (ref "R51")
      (value "4K7")
      (footprint "eagle-import:0207_12")
      (libsource (lib "eagle-import") (part "R-EU_0207/12"))
    )
    (comp (ref "R52")
      (value "22K")
      (footprint "eagle-import:0207_5V")
      (libsource (lib "eagle-import") (part "R-EU_0207/5V"))
    )
    (comp (ref "R53")
      (value "47K")
      (footprint "eagle-import:0207_12")
      (libsource (lib "eagle-import") (part "R-EU_0207/12"))
    )
    (comp (ref "R54")
      (value "39K")
      (footprint "eagle-import:0207_12")
      (libsource (lib "eagle-import") (part "R-EU_0207/12"))
    )
    (comp (ref "R55")
      (value "1K")
      (footprint "eagle-import:0207_5V")
      (libsource (lib "eagle-import") (part "R-EU_0207/5V"))
    )
    (comp (ref "R56")
      (value "1K")
      (footprint "eagle-import:0207_5V")
      (libsource (lib "eagle-import") (part "R-EU_0207/5V"))
    )
    (comp (ref "R57")
      (value "220")
      (footprint "eagle-import:0207_5V")
      (libsource (lib "eagle-import") (part "R-EU_0207/5V"))
    )
    (comp (ref "R58")
      (value "220")
      (footprint "eagle-import:0207_5V")
      (libsource (lib "eagle-import") (part "R-EU_0207/5V"))
    )
    (comp (ref "R59")
      (value "470")
      (footprint "eagle-import:0207_5V")
      (libsource (lib "eagle-import") (part "R-EU_0207/5V"))
    )
    (comp (ref "R60")
      (value "?")
      (footprint "eagle-import:0207_5V")
      (libsource (lib "eagle-import") (part "R-EU_0207/5V"))
    )
    (comp (ref "R63")
      (value "4K7")
      (footprint "eagle-import:0207_12")
      (libsource (lib "eagle-import") (part "R-EU_0207/12"))
    )
    (comp (ref "R64")
      (value "4K7")
      (footprint "eagle-import:0207_12")
      (libsource (lib "eagle-import") (part "R-EU_0207/12"))
    )
    (comp (ref "R65")
      (value "1K")
      (footprint "eagle-import:0207_12")
      (libsource (lib "eagle-import") (part "R-EU_0207/12"))
    )
    (comp (ref "R66")
      (value "470")
      (footprint "eagle-import:0207_12")
      (libsource (lib "eagle-import") (part "R-EU_0207/12"))
    )
    (comp (ref "R67")
      (value "470")
      (footprint "eagle-import:0207_12")
      (libsource (lib "eagle-import") (part "R-EU_0207/12"))
    )
    (comp (ref "R68")
      (value "100")
      (footprint "eagle-import:0207_12")
      (libsource (lib "eagle-import") (part "R-EU_0207/12"))
    )
    (comp (ref "R69")
      (value "100")
      (footprint "eagle-import:0207_5V")
      (libsource (lib "eagle-import") (part "R-EU_0207/5V"))
    )
    (comp (ref "R70")
      (value "100")
      (footprint "eagle-import:0207_5V")
      (libsource (lib "eagle-import") (part "R-EU_0207/5V"))
    )
    (comp (ref "R71")
      (value "3K3")
      (footprint "eagle-import:0207_5V")
      (libsource (lib "eagle-import") (part "R-EU_0207/5V"))
    )
    (comp (ref "R72")
      (value "10K")
      (footprint "eagle-import:0207_5V")
      (libsource (lib "eagle-import") (part "R-EU_0207/5V"))
    )
    (comp (ref "R73")
      (value "10K")
      (footprint "eagle-import:0207_5V")
      (libsource (lib "eagle-import") (part "R-EU_0207/5V"))
    )
    (comp (ref "R73_")
      (value "3K3")
      (footprint "eagle-import:0207_12")
      (libsource (lib "eagle-import") (part "R-EU_0207/12"))
    )
    (comp (ref "R74")
      (value "10K")
      (footprint "eagle-import:0207_5V")
      (libsource (lib "eagle-import") (part "R-EU_0207/5V"))
    )
    (comp (ref "R74_")
      (value "470")
      (footprint "eagle-import:0207_12")
      (libsource (lib "eagle-import") (part "R-EU_0207/12"))
    )
    (comp (ref "R75")
      (value "10K")
      (footprint "eagle-import:0207_12")
      (libsource (lib "eagle-import") (part "R-EU_0207/12"))
    )
    (comp (ref "TP1")
      (value "TPSQPAD1-13")
      (footprint "eagle-import:P1-13")
      (libsource (lib "eagle-import") (part "TPSQPAD1-13"))
    )
    (comp (ref "TP2")
      (value "TPSQPAD1-13")
      (footprint "eagle-import:P1-13")
      (libsource (lib "eagle-import") (part "TPSQPAD1-13"))
    )
    (comp (ref "TP3")
      (value "TPSQPAD1-13")
      (footprint "eagle-import:P1-13")
      (libsource (lib "eagle-import") (part "TPSQPAD1-13"))
    )
    (comp (ref "TP4")
      (value "TPSQPAD1-13")
      (footprint "eagle-import:P1-13")
      (libsource (lib "eagle-import") (part "TPSQPAD1-13"))
    )
    (comp (ref "TP5")
      (value "TPSQPAD1-13")
      (footprint "eagle-import:P1-13")
      (libsource (lib "eagle-import") (part "TPSQPAD1-13"))
    )
    (comp (ref "TP6")
      (value "TPSQPAD1-13")
      (footprint "eagle-import:P1-13")
      (libsource (lib "eagle-import") (part "TPSQPAD1-13"))
    )
    (comp (ref "TP7")
      (value "TPSQPAD1-13")
      (footprint "eagle-import:P1-13")
      (libsource (lib "eagle-import") (part "TPSQPAD1-13"))
    )
    (comp (ref "TP8")
      (value "TPSQPAD1-13")
      (footprint "eagle-import:P1-13")
      (libsource (lib "eagle-import") (part "TPSQPAD1-13"))
    )
    (comp (ref "TP9")
      (value "TPSQPAD1-13")
      (footprint "eagle-import:P1-13")
      (libsource (lib "eagle-import") (part "TPSQPAD1-13"))
    )
    (comp (ref "TP10")
      (value "TPSQPAD1-13")
      (footprint "eagle-import:P1-13")
      (libsource (lib "eagle-import") (part "TPSQPAD1-13"))
    )
    (comp (ref "U$1")
      (value "TK90_EDGE")
      (footprint "eagle-import:TK-EDGE")
      (libsource (lib "eagle-import") (part "TK90_EDGE"))
    )
    (comp (ref "VIDEO(RF)")
      (value "RF")
      (footprint "eagle-import:P1-13")
      (libsource (lib "eagle-import") (part "TPPAD1-13"))
    )
    (comp (ref "X2")
      (value "POWER")
      (footprint "eagle-import:MONO")
      (libsource (lib "eagle-import") (part "JACK?-MONO"))
    )
    (comp (ref "XTAL")
      (value "14.3044MHz")
      (footprint "eagle-import:HC49_S")
      (libsource (lib "eagle-import") (part "CRYSTALHC49S"))
    )
  )
  (nets
    (net (code "1") (name "+5V") (class "Default")
      (node (ref "7805") (pin "OUT") (pinfunction "OUT_OUT") (pintype "passive"))
      (node (ref "C1") (pin "+") (pinfunction "+_+") (pintype "passive"))
      (node (ref "C12") (pin "2") (pinfunction "2_2") (pintype "passive"))
      (node (ref "C13") (pin "2") (pinfunction "2_2") (pintype "passive"))
      (node (ref "C14") (pin "2") (pinfunction "2_2") (pintype "passive"))
      (node (ref "C15") (pin "1") (pinfunction "1_1") (pintype "passive"))
      (node (ref "C16") (pin "1") (pinfunction "1_1") (pintype "passive"))
      (node (ref "C18") (pin "1") (pinfunction "1_1") (pintype "passive"))
      (node (ref "C19") (pin "1") (pinfunction "1_1") (pintype "passive"))
      (node (ref "C20") (pin "1") (pinfunction "1_1") (pintype "passive"))
      (node (ref "C21") (pin "1") (pinfunction "1_1") (pintype "passive"))
      (node (ref "C22") (pin "2") (pinfunction "2_2") (pintype "passive"))
      (node (ref "C24") (pin "2") (pinfunction "2_2") (pintype "passive"))
      (node (ref "C29") (pin "2") (pinfunction "2_2") (pintype "passive"))
      (node (ref "C31") (pin "2") (pinfunction "2_2") (pintype "passive"))
      (node (ref "C32") (pin "2") (pinfunction "2_2") (pintype "passive"))
      (node (ref "C33") (pin "2") (pinfunction "2_2") (pintype "passive"))
      (node (ref "D13") (pin "C") (pinfunction "K_C") (pintype "bidirectional"))
      (node (ref "D15") (pin "C") (pinfunction "K_C") (pintype "bidirectional"))
      (node (ref "D17") (pin "C") (pinfunction "K_C") (pintype "bidirectional"))
      (node (ref "IC1") (pin "11") (pinfunction "VCC_11") (pintype "power_in"))
      (node (ref "IC10") (pin "16") (pinfunction "VCC_16") (pintype "power_in"))
      (node (ref "IC11") (pin "20") (pinfunction "VCC_20") (pintype "power_in"))
      (node (ref "IC12") (pin "3") (pinfunction "CR_BIAS_3") (pintype "input"))
      (node (ref "IC13") (pin "9") (pinfunction "A7_9") (pintype "input"))
      (node (ref "IC14") (pin "9") (pinfunction "A7_9") (pintype "input"))
      (node (ref "IC15") (pin "9") (pinfunction "A7_9") (pintype "input"))
      (node (ref "IC16") (pin "9") (pinfunction "A7_9") (pintype "input"))
      (node (ref "IC17") (pin "9") (pinfunction "A7_9") (pintype "input"))
      (node (ref "IC18") (pin "9") (pinfunction "A7_9") (pintype "input"))
      (node (ref "IC19") (pin "9") (pinfunction "A7_9") (pintype "input"))
      (node (ref "IC2") (pin "1") (pinfunction "VPP_1") (pintype "input"))
      (node (ref "IC2") (pin "28") (pinfunction "VCC_28") (pintype "power_in"))
      (node (ref "IC20") (pin "9") (pinfunction "A7_9") (pintype "input"))
      (node (ref "IC21") (pin "9") (pinfunction "VCC_9") (pintype "power_in"))
      (node (ref "IC22") (pin "9") (pinfunction "VCC_9") (pintype "power_in"))
      (node (ref "IC23") (pin "9") (pinfunction "VCC_9") (pintype "power_in"))
      (node (ref "IC24") (pin "9") (pinfunction "VCC_9") (pintype "power_in"))
      (node (ref "IC25") (pin "14") (pinfunction "VCC_14") (pintype "power_in"))
      (node (ref "IC26") (pin "1") (pinfunction "I0_1") (pintype "input"))
      (node (ref "IC26") (pin "14") (pinfunction "VCC_14") (pintype "power_in"))
      (node (ref "IC27") (pin "14") (pinfunction "VCC_14") (pintype "power_in"))
      (node (ref "IC28") (pin "14") (pinfunction "VCC_14") (pintype "power_in"))
      (node (ref "IC3") (pin "40") (pinfunction "VCC_40") (pintype "power_in"))
      (node (ref "IC4") (pin "10") (pinfunction "PRE_10") (pintype "input"))
      (node (ref "IC4") (pin "13") (pinfunction "CLR_13") (pintype "input"))
      (node (ref "IC4") (pin "14") (pinfunction "VCC_14") (pintype "power_in"))
      (node (ref "IC5") (pin "1") (pinfunction "CLR_1") (pintype "input"))
      (node (ref "IC5") (pin "10") (pinfunction "PRE_10") (pintype "input"))
      (node (ref "IC5") (pin "13") (pinfunction "CLR_13") (pintype "input"))
      (node (ref "IC5") (pin "14") (pinfunction "VCC_14") (pintype "power_in"))
      (node (ref "IC5") (pin "4") (pinfunction "PRE_4") (pintype "input"))
      (node (ref "IC6") (pin "16") (pinfunction "VCC_16") (pintype "power_in"))
      (node (ref "IC7") (pin "16") (pinfunction "VCC_16") (pintype "power_in"))
      (node (ref "IC8") (pin "16") (pinfunction "VCC_16") (pintype "power_in"))
      (node (ref "IC9") (pin "16") (pinfunction "VCC_16") (pintype "power_in"))
      (node (ref "Q1") (pin "3") (pinfunction "C_3") (pintype "passive"))
      (node (ref "R17") (pin "2") (pinfunction "2_2") (pintype "passive"))
      (node (ref "R18") (pin "2") (pinfunction "2_2") (pintype "passive"))
      (node (ref "R19") (pin "2") (pinfunction "2_2") (pintype "passive"))
      (node (ref "R20") (pin "2") (pinfunction "2_2") (pintype "passive"))
      (node (ref "R21") (pin "2") (pinfunction "2_2") (pintype "passive"))
      (node (ref "R22") (pin "2") (pinfunction "2_2") (pintype "passive"))
      (node (ref "R23") (pin "2") (pinfunction "2_2") (pintype "passive"))
      (node (ref "R24") (pin "2") (pinfunction "2_2") (pintype "passive"))
      (node (ref "R29") (pin "2") (pinfunction "2_2") (pintype "passive"))
      (node (ref "R30") (pin "1") (pinfunction "1_1") (pintype "passive"))
      (node (ref "R31") (pin "1") (pinfunction "1_1") (pintype "passive"))
      (node (ref "R32") (pin "1") (pinfunction "1_1") (pintype "passive"))
      (node (ref "R35") (pin "1") (pinfunction "1_1") (pintype "passive"))
      (node (ref "R36") (pin "1") (pinfunction "1_1") (pintype "passive"))
      (node (ref "R37") (pin "1") (pinfunction "1_1") (pintype "passive"))
      (node (ref "R38") (pin "1") (pinfunction "1_1") (pintype "passive"))
      (node (ref "R39") (pin "1") (pinfunction "1_1") (pintype "passive"))
      (node (ref "R40") (pin "2") (pinfunction "2_2") (pintype "passive"))
      (node (ref "R43") (pin "2") (pinfunction "2_2") (pintype "passive"))
      (node (ref "R48") (pin "2") (pinfunction "2_2") (pintype "passive"))
      (node (ref "R51") (pin "2") (pinfunction "2_2") (pintype "passive"))
      (node (ref "R74_") (pin "2") (pinfunction "2_2") (pintype "passive"))
      (node (ref "U$1") (pin "3A") (pinfunction "EDGE_3A") (pintype "bidirectional"))
    )
    (net (code "2") (name "+12V") (class "Default")
      (node (ref "C43") (pin "2") (pinfunction "2_2") (pintype "passive"))
      (node (ref "C53") (pin "+") (pinfunction "+_+") (pintype "passive"))
      (node (ref "D24") (pin "C") (pinfunction "K_C") (pintype "bidirectional"))
      (node (ref "IC11") (pin "5") (pinfunction "+12V_5") (pintype "power_in"))
      (node (ref "IC12") (pin "14") (pinfunction "RFVCC_14") (pintype "power_in"))
      (node (ref "IC12") (pin "16") (pinfunction "CRVCC_16") (pintype "power_in"))
      (node (ref "L1") (pin "2") (pinfunction "A_2") (pintype "passive"))
      (node (ref "R54") (pin "1") (pinfunction "1_1") (pintype "passive"))
      (node (ref "R57") (pin "1") (pinfunction "1_1") (pintype "passive"))
      (node (ref "R58") (pin "1") (pinfunction "1_1") (pintype "passive"))
      (node (ref "R59") (pin "1") (pinfunction "1_1") (pintype "passive"))
      (node (ref "R68") (pin "1") (pinfunction "1_1") (pintype "passive"))
      (node (ref "U$1") (pin "22B") (pinfunction "EDGE_22B") (pintype "bidirectional"))
    )
    (net (code "3") (name "-5V") (class "Default")
      (node (ref "C26") (pin "1") (pinfunction "1_1") (pintype "passive"))
      (node (ref "C27") (pin "1") (pinfunction "1_1") (pintype "passive"))
      (node (ref "C50") (pin "1") (pinfunction "1_1") (pintype "passive"))
      (node (ref "D21") (pin "A") (pinfunction "A_A") (pintype "bidirectional"))
      (node (ref "IC13") (pin "1") (pinfunction "VBB_1") (pintype "input"))
      (node (ref "IC14") (pin "1") (pinfunction "VBB_1") (pintype "input"))
      (node (ref "IC15") (pin "1") (pinfunction "VBB_1") (pintype "input"))
      (node (ref "IC16") (pin "1") (pinfunction "VBB_1") (pintype "input"))
      (node (ref "IC17") (pin "1") (pinfunction "VBB_1") (pintype "input"))
      (node (ref "IC18") (pin "1") (pinfunction "VBB_1") (pintype "input"))
      (node (ref "IC19") (pin "1") (pinfunction "VBB_1") (pintype "input"))
      (node (ref "IC20") (pin "1") (pinfunction "VBB_1") (pintype "input"))
      (node (ref "R67") (pin "1") (pinfunction "1_1") (pintype "passive"))
      (node (ref "U$1") (pin "20B") (pinfunction "EDGE_20B") (pintype "bidirectional"))
    )
    (net (code "4") (name "/+12V_UNREG") (class "Default")
      (node (ref "C48") (pin "1") (pinfunction "1_1") (pintype "passive"))
      (node (ref "C51") (pin "1") (pinfunction "1_1") (pintype "passive"))
      (node (ref "Q5") (pin "E") (pinfunction "E_E") (pintype "passive"))
      (node (ref "Q6") (pin "E") (pinfunction "E_E") (pintype "passive"))
      (node (ref "U$1") (pin "23B") (pinfunction "EDGE_23B") (pintype "bidirectional"))
    )
    (net (code "5") (name "/A0") (class "Default")
      (node (ref "IC1") (pin "30") (pinfunction "A0_30") (pintype "output"))
      (node (ref "IC2") (pin "10") (pinfunction "A0_10") (pintype "input"))
      (node (ref "IC7") (pin "3") (pinfunction "1B_3") (pintype "input"))
      (node (ref "IC8") (pin "3") (pinfunction "1B_3") (pintype "input"))
      (node (ref "Q1") (pin "2") (pinfunction "B_2") (pintype "passive"))
      (node (ref "U$1") (pin "9A") (pinfunction "EDGE_9A") (pintype "bidirectional"))
    )
    (net (code "6") (name "/A1") (class "Default")
      (node (ref "IC1") (pin "31") (pinfunction "A1_31") (pintype "output"))
      (node (ref "IC2") (pin "9") (pinfunction "A1_9") (pintype "input"))
      (node (ref "IC7") (pin "6") (pinfunction "2B_6") (pintype "input"))
      (node (ref "IC8") (pin "6") (pinfunction "2B_6") (pintype "input"))
      (node (ref "U$1") (pin "10A") (pinfunction "EDGE_10A") (pintype "bidirectional"))
    )
    (net (code "7") (name "/A2") (class "Default")
      (node (ref "IC1") (pin "32") (pinfunction "A2_32") (pintype "output"))
      (node (ref "IC2") (pin "8") (pinfunction "A2_8") (pintype "input"))
      (node (ref "IC7") (pin "13") (pinfunction "4B_13") (pintype "input"))
      (node (ref "IC8") (pin "13") (pinfunction "4B_13") (pintype "input"))
      (node (ref "U$1") (pin "11A") (pinfunction "EDGE_11A") (pintype "bidirectional"))
    )
    (net (code "8") (name "/A3") (class "Default")
      (node (ref "IC1") (pin "33") (pinfunction "A3_33") (pintype "output"))
      (node (ref "IC2") (pin "7") (pinfunction "A3_7") (pintype "input"))
      (node (ref "IC7") (pin "10") (pinfunction "3B_10") (pintype "input"))
      (node (ref "IC8") (pin "10") (pinfunction "3B_10") (pintype "input"))
      (node (ref "U$1") (pin "12A") (pinfunction "EDGE_12A") (pintype "bidirectional"))
    )
    (net (code "9") (name "/A4") (class "Default")
      (node (ref "IC1") (pin "34") (pinfunction "A4_34") (pintype "output"))
      (node (ref "IC2") (pin "6") (pinfunction "A4_6") (pintype "input"))
      (node (ref "IC6") (pin "6") (pinfunction "2B_6") (pintype "input"))
      (node (ref "IC9") (pin "6") (pinfunction "2B_6") (pintype "input"))
      (node (ref "U$1") (pin "24A") (pinfunction "EDGE_24A") (pintype "bidirectional"))
    )
    (net (code "10") (name "/A5") (class "Default")
      (node (ref "IC1") (pin "35") (pinfunction "A5_35") (pintype "output"))
      (node (ref "IC2") (pin "5") (pinfunction "A5_5") (pintype "input"))
      (node (ref "IC6") (pin "13") (pinfunction "4B_13") (pintype "input"))
      (node (ref "IC9") (pin "13") (pinfunction "4B_13") (pintype "input"))
      (node (ref "U$1") (pin "23A") (pinfunction "EDGE_23A") (pintype "bidirectional"))
    )
    (net (code "11") (name "/A6") (class "Default")
      (node (ref "IC1") (pin "36") (pinfunction "A6_36") (pintype "output"))
      (node (ref "IC2") (pin "4") (pinfunction "A6_4") (pintype "input"))
      (node (ref "IC21") (pin "14") (pinfunction "A0_14") (pintype "input"))
      (node (ref "IC22") (pin "14") (pinfunction "A0_14") (pintype "input"))
      (node (ref "IC23") (pin "14") (pinfunction "A0_14") (pintype "input"))
      (node (ref "IC24") (pin "14") (pinfunction "A0_14") (pintype "input"))
      (node (ref "IC5") (pin "12") (pinfunction "D_12") (pintype "input"))
      (node (ref "IC9") (pin "10") (pinfunction "3B_10") (pintype "input"))
      (node (ref "U$1") (pin "22A") (pinfunction "EDGE_22A") (pintype "bidirectional"))
    )
    (net (code "12") (name "/A7") (class "Default")
      (node (ref "IC1") (pin "37") (pinfunction "A7_37") (pintype "output"))
      (node (ref "IC2") (pin "3") (pinfunction "A7_3") (pintype "input"))
      (node (ref "IC26") (pin "12") (pinfunction "I0_12") (pintype "input"))
      (node (ref "IC8") (pin "2") (pinfunction "1A_2") (pintype "input"))
      (node (ref "U$1") (pin "21A") (pinfunction "EDGE_21A") (pintype "bidirectional"))
    )
    (net (code "13") (name "/A7'") (class "Default")
      (node (ref "IC21") (pin "10") (pinfunction "A7_10") (pintype "input"))
      (node (ref "IC22") (pin "10") (pinfunction "A7_10") (pintype "input"))
      (node (ref "IC23") (pin "10") (pinfunction "A7_10") (pintype "input"))
      (node (ref "IC24") (pin "10") (pinfunction "A7_10") (pintype "input"))
      (node (ref "IC26") (pin "8") (pinfunction "O_8") (pintype "output"))
    )
    (net (code "14") (name "/A8") (class "Default")
      (node (ref "D2") (pin "C") (pinfunction "K_C") (pintype "bidirectional"))
      (node (ref "IC1") (pin "38") (pinfunction "A8_38") (pintype "output"))
      (node (ref "IC2") (pin "25") (pinfunction "A8_25") (pintype "input"))
      (node (ref "IC7") (pin "5") (pinfunction "2A_5") (pintype "input"))
      (node (ref "IC8") (pin "5") (pinfunction "2A_5") (pintype "input"))
      (node (ref "U$1") (pin "26B") (pinfunction "EDGE_26B") (pintype "bidirectional"))
    )
    (net (code "15") (name "/A8-1") (class "Default")
      (node (ref "IC21") (pin "7") (pinfunction "A5_7") (pintype "input"))
      (node (ref "IC22") (pin "7") (pinfunction "A5_7") (pintype "input"))
      (node (ref "IC23") (pin "7") (pinfunction "A5_7") (pintype "input"))
      (node (ref "IC24") (pin "7") (pinfunction "A5_7") (pintype "input"))
      (node (ref "IC7") (pin "7") (pinfunction "2Y_7") (pintype "output"))
    )
    (net (code "16") (name "/A9") (class "Default")
      (node (ref "D3") (pin "C") (pinfunction "K_C") (pintype "bidirectional"))
      (node (ref "IC1") (pin "39") (pinfunction "A9_39") (pintype "output"))
      (node (ref "IC2") (pin "24") (pinfunction "A9_24") (pintype "input"))
      (node (ref "IC7") (pin "14") (pinfunction "4A_14") (pintype "input"))
      (node (ref "IC8") (pin "14") (pinfunction "4A_14") (pintype "input"))
      (node (ref "U$1") (pin "27A") (pinfunction "EDGE_27A") (pintype "bidirectional"))
    )
    (net (code "17") (name "/A9-2") (class "Default")
      (node (ref "IC21") (pin "8") (pinfunction "A4_8") (pintype "input"))
      (node (ref "IC22") (pin "8") (pinfunction "A4_8") (pintype "input"))
      (node (ref "IC23") (pin "8") (pinfunction "A4_8") (pintype "input"))
      (node (ref "IC24") (pin "8") (pinfunction "A4_8") (pintype "input"))
      (node (ref "IC7") (pin "12") (pinfunction "4Y_12") (pintype "output"))
    )
    (net (code "18") (name "/A10") (class "Default")
      (node (ref "D4") (pin "C") (pinfunction "K_C") (pintype "bidirectional"))
      (node (ref "IC1") (pin "40") (pinfunction "A10_40") (pintype "output"))
      (node (ref "IC2") (pin "21") (pinfunction "A10_21") (pintype "input"))
      (node (ref "IC7") (pin "11") (pinfunction "3A_11") (pintype "input"))
      (node (ref "IC8") (pin "11") (pinfunction "3A_11") (pintype "input"))
      (node (ref "U$1") (pin "27B") (pinfunction "EDGE_27B") (pintype "bidirectional"))
    )
    (net (code "19") (name "/A10-3") (class "Default")
      (node (ref "IC21") (pin "11") (pinfunction "A3_11") (pintype "input"))
      (node (ref "IC22") (pin "11") (pinfunction "A3_11") (pintype "input"))
      (node (ref "IC23") (pin "11") (pinfunction "A3_11") (pintype "input"))
      (node (ref "IC24") (pin "11") (pinfunction "A3_11") (pintype "input"))
      (node (ref "IC7") (pin "9") (pinfunction "3Y_9") (pintype "output"))
    )
    (net (code "20") (name "/A11") (class "Default")
      (node (ref "D5") (pin "C") (pinfunction "K_C") (pintype "bidirectional"))
      (node (ref "IC1") (pin "1") (pinfunction "A11_1") (pintype "output"))
      (node (ref "IC2") (pin "23") (pinfunction "A11_23") (pintype "input"))
      (node (ref "IC6") (pin "5") (pinfunction "2A_5") (pintype "input"))
      (node (ref "IC9") (pin "5") (pinfunction "2A_5") (pintype "input"))
      (node (ref "U$1") (pin "28A") (pinfunction "EDGE_28A") (pintype "bidirectional"))
    )
    (net (code "21") (name "/A11-4") (class "Default")
      (node (ref "IC21") (pin "12") (pinfunction "A2_12") (pintype "input"))
      (node (ref "IC22") (pin "12") (pinfunction "A2_12") (pintype "input"))
      (node (ref "IC23") (pin "12") (pinfunction "A2_12") (pintype "input"))
      (node (ref "IC24") (pin "12") (pinfunction "A2_12") (pintype "input"))
      (node (ref "IC6") (pin "7") (pinfunction "2Y_7") (pintype "output"))
    )
    (net (code "22") (name "/A12") (class "Default")
      (node (ref "D6") (pin "C") (pinfunction "K_C") (pintype "bidirectional"))
      (node (ref "IC1") (pin "2") (pinfunction "A12_2") (pintype "output"))
      (node (ref "IC2") (pin "2") (pinfunction "A12_2") (pintype "input"))
      (node (ref "IC6") (pin "14") (pinfunction "4A_14") (pintype "input"))
      (node (ref "IC9") (pin "14") (pinfunction "4A_14") (pintype "input"))
      (node (ref "U$1") (pin "2A") (pinfunction "EDGE_2A") (pintype "bidirectional"))
    )
    (net (code "23") (name "/A12-5") (class "Default")
      (node (ref "IC21") (pin "13") (pinfunction "A1_13") (pintype "input"))
      (node (ref "IC22") (pin "13") (pinfunction "A1_13") (pintype "input"))
      (node (ref "IC23") (pin "13") (pinfunction "A1_13") (pintype "input"))
      (node (ref "IC24") (pin "13") (pinfunction "A1_13") (pintype "input"))
      (node (ref "IC6") (pin "12") (pinfunction "4Y_12") (pintype "output"))
    )
    (net (code "24") (name "/A13") (class "Default")
      (node (ref "D7") (pin "C") (pinfunction "K_C") (pintype "bidirectional"))
      (node (ref "IC1") (pin "3") (pinfunction "A13_3") (pintype "output"))
      (node (ref "IC2") (pin "26") (pinfunction "A13_26") (pintype "input"))
      (node (ref "IC7") (pin "2") (pinfunction "1A_2") (pintype "input"))
      (node (ref "IC9") (pin "11") (pinfunction "3A_11") (pintype "input"))
      (node (ref "U$1") (pin "2B") (pinfunction "EDGE_2B") (pintype "bidirectional"))
    )
    (net (code "25") (name "/A13-0") (class "Default")
      (node (ref "IC21") (pin "6") (pinfunction "A6_6") (pintype "input"))
      (node (ref "IC22") (pin "6") (pinfunction "A6_6") (pintype "input"))
      (node (ref "IC23") (pin "6") (pinfunction "A6_6") (pintype "input"))
      (node (ref "IC24") (pin "6") (pinfunction "A6_6") (pintype "input"))
      (node (ref "IC7") (pin "4") (pinfunction "1Y_4") (pintype "output"))
    )
    (net (code "26") (name "/A14") (class "Default")
      (node (ref "D12") (pin "A") (pinfunction "A_A") (pintype "bidirectional"))
      (node (ref "D8") (pin "C") (pinfunction "K_C") (pintype "bidirectional"))
      (node (ref "IC1") (pin "4") (pinfunction "A14_4") (pintype "output"))
      (node (ref "IC25") (pin "4") (pinfunction "I0_4") (pintype "input"))
      (node (ref "IC27") (pin "12") (pinfunction "I0_12") (pintype "input"))
      (node (ref "IC28") (pin "1") (pinfunction "I_1") (pintype "input"))
      (node (ref "IC3") (pin "37") (pinfunction "A14_37") (pintype "input"))
      (node (ref "U$1") (pin "1A") (pinfunction "EDGE_1A") (pintype "bidirectional"))
    )
    (net (code "27") (name "/A15") (class "Default")
      (node (ref "D11") (pin "A") (pinfunction "A_A") (pintype "bidirectional"))
      (node (ref "D9") (pin "C") (pinfunction "K_C") (pintype "bidirectional"))
      (node (ref "IC1") (pin "5") (pinfunction "A15_5") (pintype "output"))
      (node (ref "IC25") (pin "13") (pinfunction "I1_13") (pintype "input"))
      (node (ref "IC27") (pin "13") (pinfunction "I1_13") (pintype "input"))
      (node (ref "IC3") (pin "38") (pinfunction "A15_38") (pintype "input"))
      (node (ref "U$1") (pin "1B") (pinfunction "EDGE_1B") (pintype "bidirectional"))
    )
    (net (code "28") (name "/AA0") (class "Default")
      (node (ref "IC13") (pin "5") (pinfunction "A0_5") (pintype "input"))
      (node (ref "IC14") (pin "5") (pinfunction "A0_5") (pintype "input"))
      (node (ref "IC15") (pin "5") (pinfunction "A0_5") (pintype "input"))
      (node (ref "IC16") (pin "5") (pinfunction "A0_5") (pintype "input"))
      (node (ref "IC17") (pin "5") (pinfunction "A0_5") (pintype "input"))
      (node (ref "IC18") (pin "5") (pinfunction "A0_5") (pintype "input"))
      (node (ref "IC19") (pin "5") (pinfunction "A0_5") (pintype "input"))
      (node (ref "IC20") (pin "5") (pinfunction "A0_5") (pintype "input"))
      (node (ref "IC3") (pin "9") (pinfunction "A0_9") (pintype "output"))
      (node (ref "R9") (pin "1") (pinfunction "1_1") (pintype "passive"))
    )
    (net (code "29") (name "/AA1") (class "Default")
      (node (ref "IC13") (pin "7") (pinfunction "A1_7") (pintype "input"))
      (node (ref "IC14") (pin "7") (pinfunction "A1_7") (pintype "input"))
      (node (ref "IC15") (pin "7") (pinfunction "A1_7") (pintype "input"))
      (node (ref "IC16") (pin "7") (pinfunction "A1_7") (pintype "input"))
      (node (ref "IC17") (pin "7") (pinfunction "A1_7") (pintype "input"))
      (node (ref "IC18") (pin "7") (pinfunction "A1_7") (pintype "input"))
      (node (ref "IC19") (pin "7") (pinfunction "A1_7") (pintype "input"))
      (node (ref "IC20") (pin "7") (pinfunction "A1_7") (pintype "input"))
      (node (ref "IC3") (pin "7") (pinfunction "A1_7") (pintype "output"))
      (node (ref "R11") (pin "1") (pinfunction "1_1") (pintype "passive"))
    )
    (net (code "30") (name "/AA2") (class "Default")
      (node (ref "IC13") (pin "6") (pinfunction "A2_6") (pintype "input"))
      (node (ref "IC14") (pin "6") (pinfunction "A2_6") (pintype "input"))
      (node (ref "IC15") (pin "6") (pinfunction "A2_6") (pintype "input"))
      (node (ref "IC16") (pin "6") (pinfunction "A2_6") (pintype "input"))
      (node (ref "IC17") (pin "6") (pinfunction "A2_6") (pintype "input"))
      (node (ref "IC18") (pin "6") (pinfunction "A2_6") (pintype "input"))
      (node (ref "IC19") (pin "6") (pinfunction "A2_6") (pintype "input"))
      (node (ref "IC20") (pin "6") (pinfunction "A2_6") (pintype "input"))
      (node (ref "IC3") (pin "8") (pinfunction "A2_8") (pintype "output"))
      (node (ref "R10") (pin "1") (pinfunction "1_1") (pintype "passive"))
    )
    (net (code "31") (name "/AA3") (class "Default")
      (node (ref "IC13") (pin "12") (pinfunction "A3_12") (pintype "input"))
      (node (ref "IC14") (pin "12") (pinfunction "A3_12") (pintype "input"))
      (node (ref "IC15") (pin "12") (pinfunction "A3_12") (pintype "input"))
      (node (ref "IC16") (pin "12") (pinfunction "A3_12") (pintype "input"))
      (node (ref "IC17") (pin "12") (pinfunction "A3_12") (pintype "input"))
      (node (ref "IC18") (pin "12") (pinfunction "A3_12") (pintype "input"))
      (node (ref "IC19") (pin "12") (pinfunction "A3_12") (pintype "input"))
      (node (ref "IC20") (pin "12") (pinfunction "A3_12") (pintype "input"))
      (node (ref "IC3") (pin "4") (pinfunction "A3_4") (pintype "output"))
      (node (ref "R14") (pin "1") (pinfunction "1_1") (pintype "passive"))
    )
    (net (code "32") (name "/AA4") (class "Default")
      (node (ref "IC13") (pin "11") (pinfunction "A4_11") (pintype "input"))
      (node (ref "IC14") (pin "11") (pinfunction "A4_11") (pintype "input"))
      (node (ref "IC15") (pin "11") (pinfunction "A4_11") (pintype "input"))
      (node (ref "IC16") (pin "11") (pinfunction "A4_11") (pintype "input"))
      (node (ref "IC17") (pin "11") (pinfunction "A4_11") (pintype "input"))
      (node (ref "IC18") (pin "11") (pinfunction "A4_11") (pintype "input"))
      (node (ref "IC19") (pin "11") (pinfunction "A4_11") (pintype "input"))
      (node (ref "IC20") (pin "11") (pinfunction "A4_11") (pintype "input"))
      (node (ref "IC3") (pin "5") (pinfunction "A4_5") (pintype "output"))
      (node (ref "R13") (pin "1") (pinfunction "1_1") (pintype "passive"))
    )
    (net (code "33") (name "/AA5") (class "Default")
      (node (ref "IC13") (pin "10") (pinfunction "A5_10") (pintype "input"))
      (node (ref "IC14") (pin "10") (pinfunction "A5_10") (pintype "input"))
      (node (ref "IC15") (pin "10") (pinfunction "A5_10") (pintype "input"))
      (node (ref "IC16") (pin "10") (pinfunction "A5_10") (pintype "input"))
      (node (ref "IC17") (pin "10") (pinfunction "A5_10") (pintype "input"))
      (node (ref "IC18") (pin "10") (pinfunction "A5_10") (pintype "input"))
      (node (ref "IC19") (pin "10") (pinfunction "A5_10") (pintype "input"))
      (node (ref "IC20") (pin "10") (pinfunction "A5_10") (pintype "input"))
      (node (ref "IC3") (pin "6") (pinfunction "A5_6") (pintype "output"))
      (node (ref "R12") (pin "1") (pinfunction "1_1") (pintype "passive"))
    )
    (net (code "34") (name "/AA6") (class "Default")
      (node (ref "IC13") (pin "13") (pinfunction "A6_13") (pintype "input"))
      (node (ref "IC14") (pin "13") (pinfunction "A6_13") (pintype "input"))
      (node (ref "IC15") (pin "13") (pinfunction "A6_13") (pintype "input"))
      (node (ref "IC16") (pin "13") (pinfunction "A6_13") (pintype "input"))
      (node (ref "IC17") (pin "13") (pinfunction "A6_13") (pintype "input"))
      (node (ref "IC18") (pin "13") (pinfunction "A6_13") (pintype "input"))
      (node (ref "IC19") (pin "13") (pinfunction "A6_13") (pintype "input"))
      (node (ref "IC20") (pin "13") (pinfunction "A6_13") (pintype "input"))
      (node (ref "IC3") (pin "3") (pinfunction "A6_3") (pintype "output"))
      (node (ref "R15") (pin "1") (pinfunction "1_1") (pintype "passive"))
    )
    (net (code "35") (name "/CARRIER") (class "Default")
      (node (ref "C47") (pin "1") (pinfunction "1_1") (pintype "passive"))
      (node (ref "D17") (pin "A") (pinfunction "A_A") (pintype "bidirectional"))
      (node (ref "D18") (pin "C") (pinfunction "K_C") (pintype "bidirectional"))
      (node (ref "IC3") (pin "39") (pinfunction "CARRIER_39") (pintype "output"))
      (node (ref "R64") (pin "2") (pinfunction "2_2") (pintype "passive"))
      (node (ref "R71") (pin "2") (pinfunction "2_2") (pintype "passive"))
    )
    (net (code "36") (name "/CLK") (class "Default")
      (node (ref "C9") (pin "2") (pinfunction "2_2") (pintype "passive"))
      (node (ref "IC3") (pin "36") (pinfunction "CKOUT_36") (pintype "output"))
      (node (ref "R49") (pin "2") (pinfunction "2_2") (pintype "passive"))
      (node (ref "R51") (pin "1") (pinfunction "1_1") (pintype "passive"))
      (node (ref "U$1") (pin "8A") (pinfunction "EDGE_8A") (pintype "bidirectional"))
    )
    (net (code "37") (name "/D0") (class "Default")
      (node (ref "IC1") (pin "14") (pinfunction "D0_14") (pintype "bidirectional"))
      (node (ref "IC10") (pin "3") (pinfunction "Y1_3") (pintype "tri_state"))
      (node (ref "IC2") (pin "11") (pinfunction "O0_11") (pintype "tri_state"))
      (node (ref "IC21") (pin "2") (pinfunction "I/O1_2") (pintype "bidirectional"))
      (node (ref "IC23") (pin "2") (pinfunction "I/O1_2") (pintype "bidirectional"))
      (node (ref "R1") (pin "2") (pinfunction "2_2") (pintype "passive"))
      (node (ref "R17") (pin "1") (pinfunction "1_1") (pintype "passive"))
      (node (ref "U$1") (pin "6B") (pinfunction "EDGE_6B") (pintype "bidirectional"))
    )
    (net (code "38") (name "/D0'") (class "Default")
      (node (ref "IC20") (pin "14") (pinfunction "DO_14") (pintype "bidirectional"))
      (node (ref "IC20") (pin "2") (pinfunction "DI_2") (pintype "bidirectional"))
      (node (ref "IC3") (pin "25") (pinfunction "D0_25") (pintype "bidirectional"))
      (node (ref "R1") (pin "1") (pinfunction "1_1") (pintype "passive"))
    )
    (net (code "39") (name "/D1") (class "Default")
      (node (ref "IC1") (pin "15") (pinfunction "D1_15") (pintype "bidirectional"))
      (node (ref "IC10") (pin "5") (pinfunction "Y2_5") (pintype "tri_state"))
      (node (ref "IC2") (pin "12") (pinfunction "O1_12") (pintype "tri_state"))
      (node (ref "IC21") (pin "3") (pinfunction "I/O2_3") (pintype "bidirectional"))
      (node (ref "IC23") (pin "3") (pinfunction "I/O2_3") (pintype "bidirectional"))
      (node (ref "R18") (pin "1") (pinfunction "1_1") (pintype "passive"))
      (node (ref "R2") (pin "2") (pinfunction "2_2") (pintype "passive"))
      (node (ref "U$1") (pin "7B") (pinfunction "EDGE_7B") (pintype "bidirectional"))
    )
    (net (code "40") (name "/D1'") (class "Default")
      (node (ref "IC19") (pin "14") (pinfunction "DO_14") (pintype "bidirectional"))
      (node (ref "IC19") (pin "2") (pinfunction "DI_2") (pintype "bidirectional"))
      (node (ref "IC3") (pin "26") (pinfunction "D1_26") (pintype "bidirectional"))
      (node (ref "R2") (pin "1") (pinfunction "1_1") (pintype "passive"))
    )
    (net (code "41") (name "/D2") (class "Default")
      (node (ref "IC1") (pin "12") (pinfunction "D2_12") (pintype "bidirectional"))
      (node (ref "IC10") (pin "7") (pinfunction "Y3_7") (pintype "tri_state"))
      (node (ref "IC2") (pin "13") (pinfunction "O2_13") (pintype "tri_state"))
      (node (ref "IC21") (pin "15") (pinfunction "I/O3_15") (pintype "bidirectional"))
      (node (ref "IC23") (pin "15") (pinfunction "I/O3_15") (pintype "bidirectional"))
      (node (ref "R19") (pin "1") (pinfunction "1_1") (pintype "passive"))
      (node (ref "R3") (pin "2") (pinfunction "2_2") (pintype "passive"))
      (node (ref "U$1") (pin "8B") (pinfunction "EDGE_8B") (pintype "bidirectional"))
    )
    (net (code "42") (name "/D2'") (class "Default")
      (node (ref "IC18") (pin "14") (pinfunction "DO_14") (pintype "bidirectional"))
      (node (ref "IC18") (pin "2") (pinfunction "DI_2") (pintype "bidirectional"))
      (node (ref "IC3") (pin "27") (pinfunction "D2_27") (pintype "bidirectional"))
      (node (ref "R3") (pin "1") (pinfunction "1_1") (pintype "passive"))
    )
    (net (code "43") (name "/D3") (class "Default")
      (node (ref "IC1") (pin "8") (pinfunction "D3_8") (pintype "bidirectional"))
      (node (ref "IC10") (pin "9") (pinfunction "Y4_9") (pintype "tri_state"))
      (node (ref "IC2") (pin "15") (pinfunction "O3_15") (pintype "tri_state"))
      (node (ref "IC21") (pin "17") (pinfunction "I/O4_17") (pintype "bidirectional"))
      (node (ref "IC23") (pin "17") (pinfunction "I/O4_17") (pintype "bidirectional"))
      (node (ref "R20") (pin "1") (pinfunction "1_1") (pintype "passive"))
      (node (ref "R4") (pin "2") (pinfunction "2_2") (pintype "passive"))
      (node (ref "U$1") (pin "11B") (pinfunction "EDGE_11B") (pintype "bidirectional"))
    )
    (net (code "44") (name "/D3'") (class "Default")
      (node (ref "IC17") (pin "14") (pinfunction "DO_14") (pintype "bidirectional"))
      (node (ref "IC17") (pin "2") (pinfunction "DI_2") (pintype "bidirectional"))
      (node (ref "IC3") (pin "28") (pinfunction "D3_28") (pintype "bidirectional"))
      (node (ref "R4") (pin "1") (pinfunction "1_1") (pintype "passive"))
    )
    (net (code "45") (name "/D4") (class "Default")
      (node (ref "IC1") (pin "7") (pinfunction "D4_7") (pintype "bidirectional"))
      (node (ref "IC10") (pin "11") (pinfunction "Y5_11") (pintype "tri_state"))
      (node (ref "IC2") (pin "16") (pinfunction "O4_16") (pintype "tri_state"))
      (node (ref "IC22") (pin "2") (pinfunction "I/O1_2") (pintype "bidirectional"))
      (node (ref "IC24") (pin "2") (pinfunction "I/O1_2") (pintype "bidirectional"))
      (node (ref "R21") (pin "1") (pinfunction "1_1") (pintype "passive"))
      (node (ref "R5") (pin "2") (pinfunction "2_2") (pintype "passive"))
      (node (ref "U$1") (pin "12B") (pinfunction "EDGE_12B") (pintype "bidirectional"))
    )
    (net (code "46") (name "/D4'") (class "Default")
      (node (ref "IC16") (pin "14") (pinfunction "DO_14") (pintype "bidirectional"))
      (node (ref "IC16") (pin "2") (pinfunction "DI_2") (pintype "bidirectional"))
      (node (ref "IC3") (pin "29") (pinfunction "D4_29") (pintype "bidirectional"))
      (node (ref "R5") (pin "1") (pinfunction "1_1") (pintype "passive"))
    )
    (net (code "47") (name "/D5") (class "Default")
      (node (ref "IC1") (pin "9") (pinfunction "D5_9") (pintype "bidirectional"))
      (node (ref "IC2") (pin "17") (pinfunction "O5_17") (pintype "tri_state"))
      (node (ref "IC22") (pin "3") (pinfunction "I/O2_3") (pintype "bidirectional"))
      (node (ref "IC24") (pin "3") (pinfunction "I/O2_3") (pintype "bidirectional"))
      (node (ref "R22") (pin "1") (pinfunction "1_1") (pintype "passive"))
      (node (ref "R6") (pin "2") (pinfunction "2_2") (pintype "passive"))
      (node (ref "U$1") (pin "10B") (pinfunction "EDGE_10B") (pintype "bidirectional"))
    )
    (net (code "48") (name "/D5'") (class "Default")
      (node (ref "IC15") (pin "14") (pinfunction "DO_14") (pintype "bidirectional"))
      (node (ref "IC15") (pin "2") (pinfunction "DI_2") (pintype "bidirectional"))
      (node (ref "IC3") (pin "30") (pinfunction "D5_30") (pintype "bidirectional"))
      (node (ref "R6") (pin "1") (pinfunction "1_1") (pintype "passive"))
    )
    (net (code "49") (name "/D6") (class "Default")
      (node (ref "IC1") (pin "10") (pinfunction "D6_10") (pintype "bidirectional"))
      (node (ref "IC10") (pin "13") (pinfunction "Y6_13") (pintype "tri_state"))
      (node (ref "IC2") (pin "18") (pinfunction "O6_18") (pintype "tri_state"))
      (node (ref "IC22") (pin "15") (pinfunction "I/O3_15") (pintype "bidirectional"))
      (node (ref "IC24") (pin "15") (pinfunction "I/O3_15") (pintype "bidirectional"))
      (node (ref "R23") (pin "1") (pinfunction "1_1") (pintype "passive"))
      (node (ref "R7") (pin "2") (pinfunction "2_2") (pintype "passive"))
      (node (ref "U$1") (pin "9B") (pinfunction "EDGE_9B") (pintype "bidirectional"))
    )
    (net (code "50") (name "/D6'") (class "Default")
      (node (ref "IC14") (pin "14") (pinfunction "DO_14") (pintype "bidirectional"))
      (node (ref "IC14") (pin "2") (pinfunction "DI_2") (pintype "bidirectional"))
      (node (ref "IC3") (pin "31") (pinfunction "D6_31") (pintype "bidirectional"))
      (node (ref "R7") (pin "1") (pinfunction "1_1") (pintype "passive"))
    )
    (net (code "51") (name "/D7") (class "Default")
      (node (ref "D1") (pin "A") (pinfunction "A_A") (pintype "bidirectional"))
      (node (ref "IC1") (pin "13") (pinfunction "D7_13") (pintype "bidirectional"))
      (node (ref "IC2") (pin "19") (pinfunction "O7_19") (pintype "tri_state"))
      (node (ref "IC22") (pin "17") (pinfunction "I/O4_17") (pintype "bidirectional"))
      (node (ref "IC24") (pin "17") (pinfunction "I/O4_17") (pintype "bidirectional"))
      (node (ref "R24") (pin "1") (pinfunction "1_1") (pintype "passive"))
      (node (ref "R8") (pin "2") (pinfunction "2_2") (pintype "passive"))
      (node (ref "U$1") (pin "3B") (pinfunction "EDGE_3B") (pintype "bidirectional"))
    )
    (net (code "52") (name "/D7'") (class "Default")
      (node (ref "IC13") (pin "14") (pinfunction "DO_14") (pintype "bidirectional"))
      (node (ref "IC13") (pin "2") (pinfunction "DI_2") (pintype "bidirectional"))
      (node (ref "IC3") (pin "32") (pinfunction "D7_32") (pintype "bidirectional"))
      (node (ref "R8") (pin "1") (pinfunction "1_1") (pintype "passive"))
    )
    (net (code "53") (name "/MREQ'") (class "Default")
      (node (ref "D10") (pin "C") (pinfunction "K_C") (pintype "bidirectional"))
      (node (ref "IC3") (pin "15") (pinfunction "~{MREQ}_15") (pintype "input"))
      (node (ref "R34") (pin "2") (pinfunction "2_2") (pintype "passive"))
    )
    (net (code "54") (name "/RESET") (class "Default")
      (node (ref "D10") (pin "A") (pinfunction "A_A") (pintype "bidirectional"))
      (node (ref "IC28") (pin "12") (pinfunction "O_12") (pintype "output"))
    )
    (net (code "55") (name "/SNDIN") (class "Default")
      (node (ref "C54") (pin "1") (pinfunction "1_1") (pintype "passive"))
      (node (ref "C57") (pin "1") (pinfunction "1_1") (pintype "passive"))
      (node (ref "D13") (pin "A") (pinfunction "A_A") (pintype "bidirectional"))
      (node (ref "D14") (pin "C") (pinfunction "C_C") (pintype "passive"))
      (node (ref "Q7") (pin "2") (pinfunction "B_2") (pintype "passive"))
      (node (ref "R40") (pin "1") (pinfunction "1_1") (pintype "passive"))
      (node (ref "R41") (pin "2") (pinfunction "2_2") (pintype "passive"))
      (node (ref "R42") (pin "2") (pinfunction "2_2") (pintype "passive"))
      (node (ref "TP3") (pin "1") (pinfunction "TP_1") (pintype "input"))
    )
    (net (code "56") (name "/{slash}INT") (class "Default")
      (node (ref "IC1") (pin "16") (pinfunction "~{INT}_16") (pintype "input"))
      (node (ref "R25") (pin "2") (pinfunction "2_2") (pintype "passive"))
      (node (ref "TP10") (pin "1") (pinfunction "TP_1") (pintype "input"))
      (node (ref "U$1") (pin "13B") (pinfunction "EDGE_13B") (pintype "bidirectional"))
    )
    (net (code "57") (name "/~{A}{slash}B") (class "Default")
      (node (ref "IC27") (pin "3") (pinfunction "O_3") (pintype "output"))
      (node (ref "IC6") (pin "1") (pinfunction "~{A}/B_1") (pintype "input"))
      (node (ref "IC7") (pin "1") (pinfunction "~{A}/B_1") (pintype "input"))
      (node (ref "R45") (pin "1") (pinfunction "1_1") (pintype "passive"))
    )
    (net (code "58") (name "/~{CAS0}") (class "Default")
      (node (ref "IC23") (pin "1") (pinfunction "~{OE}_1") (pintype "input"))
      (node (ref "IC23") (pin "16") (pinfunction "~{CAS}_16") (pintype "input"))
      (node (ref "IC24") (pin "1") (pinfunction "~{OE}_1") (pintype "input"))
      (node (ref "IC24") (pin "16") (pinfunction "~{CAS}_16") (pintype "input"))
      (node (ref "IC25") (pin "8") (pinfunction "O_8") (pintype "output"))
    )
    (net (code "59") (name "/~{CAS1}") (class "Default")
      (node (ref "IC21") (pin "1") (pinfunction "~{OE}_1") (pintype "input"))
      (node (ref "IC21") (pin "16") (pinfunction "~{CAS}_16") (pintype "input"))
      (node (ref "IC22") (pin "1") (pinfunction "~{OE}_1") (pintype "input"))
      (node (ref "IC22") (pin "16") (pinfunction "~{CAS}_16") (pintype "input"))
      (node (ref "IC25") (pin "6") (pinfunction "O_6") (pintype "output"))
    )
    (net (code "60") (name "/~{IORQGE}") (class "Default")
      (node (ref "IC3") (pin "2") (pinfunction "~{CS}_2") (pintype "input"))
      (node (ref "Q1") (pin "1") (pinfunction "E_1") (pintype "passive"))
      (node (ref "R27") (pin "2") (pinfunction "2_2") (pintype "passive"))
      (node (ref "U$1") (pin "13A") (pinfunction "EDGE_13A") (pintype "bidirectional"))
    )
    (net (code "61") (name "/~{IORQ}") (class "Default")
      (node (ref "IC1") (pin "20") (pinfunction "~{IORQ}_20") (pintype "output"))
      (node (ref "R27") (pin "1") (pinfunction "1_1") (pintype "passive"))
      (node (ref "U$1") (pin "17B") (pinfunction "EDGE_17B") (pintype "bidirectional"))
    )
    (net (code "62") (name "/~{KBD}") (class "Default")
      (node (ref "D1") (pin "C") (pinfunction "K_C") (pintype "bidirectional"))
      (node (ref "IC10") (pin "1") (pinfunction "G1_1") (pintype "input"))
      (node (ref "IC3") (pin "10") (pinfunction "~{KBD}_10") (pintype "output"))
    )
    (net (code "63") (name "/~{MREQ}") (class "Default")
      (node (ref "IC1") (pin "19") (pinfunction "~{MREQ}_19") (pintype "output"))
      (node (ref "IC2") (pin "22") (pinfunction "~{OE}_22") (pintype "input"))
      (node (ref "IC27") (pin "4") (pinfunction "I0_4") (pintype "input"))
      (node (ref "R34") (pin "1") (pinfunction "1_1") (pintype "passive"))
      (node (ref "U$1") (pin "16B") (pinfunction "EDGE_16B") (pintype "bidirectional"))
    )
    (net (code "64") (name "/~{RAS}") (class "Default")
      (node (ref "IC21") (pin "5") (pinfunction "~{RAS}_5") (pintype "input"))
      (node (ref "IC22") (pin "5") (pinfunction "~{RAS}_5") (pintype "input"))
      (node (ref "IC23") (pin "5") (pinfunction "~{RAS}_5") (pintype "input"))
      (node (ref "IC24") (pin "5") (pinfunction "~{RAS}_5") (pintype "input"))
      (node (ref "IC27") (pin "6") (pinfunction "O_6") (pintype "output"))
      (node (ref "IC27") (pin "9") (pinfunction "I0_9") (pintype "input"))
      (node (ref "R28") (pin "1") (pinfunction "1_1") (pintype "passive"))
    )
    (net (code "65") (name "/~{RD}") (class "Default")
      (node (ref "IC1") (pin "21") (pinfunction "~{RD}_21") (pintype "output"))
      (node (ref "IC2") (pin "27") (pinfunction "~{PGM}_27") (pintype "input"))
      (node (ref "IC25") (pin "2") (pinfunction "I1_2") (pintype "input"))
      (node (ref "IC3") (pin "17") (pinfunction "~{RD}_17") (pintype "input"))
      (node (ref "U$1") (pin "18B") (pinfunction "EDGE_18B") (pintype "bidirectional"))
    )
    (net (code "66") (name "/~{RESET}") (class "Default")
      (node (ref "C17") (pin "1") (pinfunction "1_1") (pintype "passive"))
      (node (ref "IC1") (pin "26") (pinfunction "~{RESET}_26") (pintype "input"))
      (node (ref "IC28") (pin "13") (pinfunction "I_13") (pintype "input"))
      (node (ref "R29") (pin "1") (pinfunction "1_1") (pintype "passive"))
      (node (ref "U$1") (pin "20A") (pinfunction "EDGE_20A") (pintype "bidirectional"))
    )
    (net (code "67") (name "/~{RFSH}") (class "Default")
      (node (ref "IC1") (pin "28") (pinfunction "~{RFSH}_28") (pintype "output"))
      (node (ref "IC26") (pin "13") (pinfunction "I1_13") (pintype "input"))
      (node (ref "IC26") (pin "2") (pinfunction "I1_2") (pintype "input"))
      (node (ref "IC5") (pin "11") (pinfunction "CLK_11") (pintype "input"))
      (node (ref "U$1") (pin "25B") (pinfunction "EDGE_25B") (pintype "bidirectional"))
    )
    (net (code "68") (name "/~{ROMCS}") (class "Default")
      (node (ref "IC2") (pin "20") (pinfunction "~{CE}_20") (pintype "input"))
      (node (ref "R26") (pin "2") (pinfunction "2_2") (pintype "passive"))
      (node (ref "TP9") (pin "1") (pinfunction "TP_1") (pintype "input"))
      (node (ref "U$1") (pin "25A") (pinfunction "EDGE_25A") (pintype "bidirectional"))
    )
    (net (code "69") (name "/~{ULAINT}") (class "Default")
      (node (ref "IC3") (pin "34") (pinfunction "~{INT}_34") (pintype "output"))
      (node (ref "R25") (pin "1") (pinfunction "1_1") (pintype "passive"))
    )
    (net (code "70") (name "/~{VCAS}") (class "Default")
      (node (ref "IC13") (pin "15") (pinfunction "~{CAS}_15") (pintype "input"))
      (node (ref "IC14") (pin "15") (pinfunction "~{CAS}_15") (pintype "input"))
      (node (ref "IC15") (pin "15") (pinfunction "~{CAS}_15") (pintype "input"))
      (node (ref "IC16") (pin "15") (pinfunction "~{CAS}_15") (pintype "input"))
      (node (ref "IC17") (pin "15") (pinfunction "~{CAS}_15") (pintype "input"))
      (node (ref "IC18") (pin "15") (pinfunction "~{CAS}_15") (pintype "input"))
      (node (ref "IC19") (pin "15") (pinfunction "~{CAS}_15") (pintype "input"))
      (node (ref "IC20") (pin "15") (pinfunction "~{CAS}_15") (pintype "input"))
      (node (ref "IC3") (pin "12") (pinfunction "~{VCAS}_12") (pintype "output"))
      (node (ref "TP5") (pin "1") (pinfunction "TP_1") (pintype "input"))
    )
    (net (code "71") (name "/~{VRAS}") (class "Default")
      (node (ref "IC13") (pin "4") (pinfunction "~{RAS}_4") (pintype "input"))
      (node (ref "IC14") (pin "4") (pinfunction "~{RAS}_4") (pintype "input"))
      (node (ref "IC15") (pin "4") (pinfunction "~{RAS}_4") (pintype "input"))
      (node (ref "IC16") (pin "4") (pinfunction "~{RAS}_4") (pintype "input"))
      (node (ref "IC17") (pin "4") (pinfunction "~{RAS}_4") (pintype "input"))
      (node (ref "IC18") (pin "4") (pinfunction "~{RAS}_4") (pintype "input"))
      (node (ref "IC19") (pin "4") (pinfunction "~{RAS}_4") (pintype "input"))
      (node (ref "IC20") (pin "4") (pinfunction "~{RAS}_4") (pintype "input"))
      (node (ref "IC3") (pin "13") (pinfunction "~{VRAS}_13") (pintype "output"))
      (node (ref "R16") (pin "2") (pinfunction "2_2") (pintype "passive"))
      (node (ref "TP4") (pin "1") (pinfunction "TP_1") (pintype "input"))
    )
    (net (code "72") (name "/~{VWR}") (class "Default")
      (node (ref "IC13") (pin "3") (pinfunction "~{WE}_3") (pintype "input"))
      (node (ref "IC14") (pin "3") (pinfunction "~{WE}_3") (pintype "input"))
      (node (ref "IC15") (pin "3") (pinfunction "~{WE}_3") (pintype "input"))
      (node (ref "IC16") (pin "3") (pinfunction "~{WE}_3") (pintype "input"))
      (node (ref "IC17") (pin "3") (pinfunction "~{WE}_3") (pintype "input"))
      (node (ref "IC18") (pin "3") (pinfunction "~{WE}_3") (pintype "input"))
      (node (ref "IC19") (pin "3") (pinfunction "~{WE}_3") (pintype "input"))
      (node (ref "IC20") (pin "3") (pinfunction "~{WE}_3") (pintype "input"))
      (node (ref "IC3") (pin "14") (pinfunction "~{VWR}_14") (pintype "output"))
      (node (ref "TP6") (pin "1") (pinfunction "TP_1") (pintype "input"))
    )
    (net (code "73") (name "/~{WR}") (class "Default")
      (node (ref "IC1") (pin "22") (pinfunction "~{WR}_22") (pintype "output"))
      (node (ref "IC21") (pin "4") (pinfunction "~{WE}_4") (pintype "input"))
      (node (ref "IC22") (pin "4") (pinfunction "~{WE}_4") (pintype "input"))
      (node (ref "IC23") (pin "4") (pinfunction "~{WE}_4") (pintype "input"))
      (node (ref "IC24") (pin "4") (pinfunction "~{WE}_4") (pintype "input"))
      (node (ref "IC25") (pin "1") (pinfunction "I0_1") (pintype "input"))
      (node (ref "IC3") (pin "16") (pinfunction "~{WR}_16") (pintype "input"))
      (node (ref "U$1") (pin "19B") (pinfunction "EDGE_19B") (pintype "bidirectional"))
    )
    (net (code "74") (name "GND") (class "Default")
      (node (ref "7805") (pin "GND") (pinfunction "GND_GND") (pintype "input"))
      (node (ref "C1") (pin "-") (pinfunction "-_-") (pintype "passive"))
      (node (ref "C10") (pin "2") (pinfunction "2_2") (pintype "passive"))
      (node (ref "C11") (pin "2") (pinfunction "2_2") (pintype "passive"))
      (node (ref "C12") (pin "1") (pinfunction "1_1") (pintype "passive"))
      (node (ref "C13") (pin "1") (pinfunction "1_1") (pintype "passive"))
      (node (ref "C14") (pin "1") (pinfunction "1_1") (pintype "passive"))
      (node (ref "C15") (pin "2") (pinfunction "2_2") (pintype "passive"))
      (node (ref "C16") (pin "2") (pinfunction "2_2") (pintype "passive"))
      (node (ref "C17") (pin "2") (pinfunction "2_2") (pintype "passive"))
      (node (ref "C18") (pin "2") (pinfunction "2_2") (pintype "passive"))
      (node (ref "C19") (pin "2") (pinfunction "2_2") (pintype "passive"))
      (node (ref "C2") (pin "-") (pinfunction "-_-") (pintype "passive"))
      (node (ref "C20") (pin "2") (pinfunction "2_2") (pintype "passive"))
      (node (ref "C21") (pin "2") (pinfunction "2_2") (pintype "passive"))
      (node (ref "C22") (pin "1") (pinfunction "1_1") (pintype "passive"))
      (node (ref "C23") (pin "2") (pinfunction "2_2") (pintype "passive"))
      (node (ref "C24") (pin "1") (pinfunction "1_1") (pintype "passive"))
      (node (ref "C25") (pin "2") (pinfunction "2_2") (pintype "passive"))
      (node (ref "C26") (pin "2") (pinfunction "2_2") (pintype "passive"))
      (node (ref "C27") (pin "2") (pinfunction "2_2") (pintype "passive"))
      (node (ref "C28") (pin "2") (pinfunction "2_2") (pintype "passive"))
      (node (ref "C29") (pin "1") (pinfunction "1_1") (pintype "passive"))
      (node (ref "C3") (pin "1") (pinfunction "1_1") (pintype "passive"))
      (node (ref "C30") (pin "2") (pinfunction "2_2") (pintype "passive"))
      (node (ref "C31") (pin "1") (pinfunction "1_1") (pintype "passive"))
      (node (ref "C32") (pin "1") (pinfunction "1_1") (pintype "passive"))
      (node (ref "C33") (pin "1") (pinfunction "1_1") (pintype "passive"))
      (node (ref "C40") (pin "1") (pinfunction "1_1") (pintype "passive"))
      (node (ref "C43") (pin "1") (pinfunction "1_1") (pintype "passive"))
      (node (ref "C44") (pin "2") (pinfunction "2_2") (pintype "passive"))
      (node (ref "C45") (pin "2") (pinfunction "2_2") (pintype "passive"))
      (node (ref "C46") (pin "2") (pinfunction "2_2") (pintype "passive"))
      (node (ref "C49") (pin "+") (pinfunction "+_+") (pintype "passive"))
      (node (ref "C50") (pin "2") (pinfunction "2_2") (pintype "passive"))
      (node (ref "C52") (pin "-") (pinfunction "-_-") (pintype "passive"))
      (node (ref "C53") (pin "-") (pinfunction "-_-") (pintype "passive"))
      (node (ref "C56") (pin "1") (pinfunction "1_1") (pintype "passive"))
      (node (ref "C57") (pin "2") (pinfunction "2_2") (pintype "passive"))
      (node (ref "C6") (pin "1") (pinfunction "1_1") (pintype "passive"))
      (node (ref "C8") (pin "1") (pinfunction "1_1") (pintype "passive"))
      (node (ref "D14") (pin "A") (pinfunction "A_A") (pintype "passive"))
      (node (ref "D16") (pin "A") (pinfunction "A_A") (pintype "bidirectional"))
      (node (ref "D18") (pin "A") (pinfunction "A_A") (pintype "bidirectional"))
      (node (ref "D20") (pin "C") (pinfunction "K_C") (pintype "bidirectional"))
      (node (ref "D21") (pin "C") (pinfunction "K_C") (pintype "bidirectional"))
      (node (ref "D24") (pin "A") (pinfunction "A_A") (pintype "bidirectional"))
      (node (ref "EAR") (pin "RING") (pinfunction "SHIELD_RING") (pintype "passive"))
      (node (ref "IC1") (pin "29") (pinfunction "GND_29") (pintype "power_in"))
      (node (ref "IC10") (pin "15") (pinfunction "G2_15") (pintype "input"))
      (node (ref "IC10") (pin "8") (pinfunction "GND_8") (pintype "power_in"))
      (node (ref "IC11") (pin "10") (pinfunction "GND_10") (pintype "power_in"))
      (node (ref "IC12") (pin "5") (pinfunction "GND_5") (pintype "power_in"))
      (node (ref "IC13") (pin "16") (pinfunction "VSS_16") (pintype "power_in"))
      (node (ref "IC14") (pin "16") (pinfunction "VSS_16") (pintype "power_in"))
      (node (ref "IC15") (pin "16") (pinfunction "VSS_16") (pintype "power_in"))
      (node (ref "IC16") (pin "16") (pinfunction "VSS_16") (pintype "power_in"))
      (node (ref "IC17") (pin "16") (pinfunction "VSS_16") (pintype "power_in"))
      (node (ref "IC18") (pin "16") (pinfunction "VSS_16") (pintype "power_in"))
      (node (ref "IC19") (pin "16") (pinfunction "VSS_16") (pintype "power_in"))
      (node (ref "IC2") (pin "14") (pinfunction "GND_14") (pintype "power_in"))
      (node (ref "IC20") (pin "16") (pinfunction "VSS_16") (pintype "power_in"))
      (node (ref "IC21") (pin "18") (pinfunction "GND_18") (pintype "power_in"))
      (node (ref "IC22") (pin "18") (pinfunction "GND_18") (pintype "power_in"))
      (node (ref "IC23") (pin "18") (pinfunction "GND_18") (pintype "power_in"))
      (node (ref "IC24") (pin "18") (pinfunction "GND_18") (pintype "power_in"))
      (node (ref "IC25") (pin "7") (pinfunction "GND_7") (pintype "power_in"))
      (node (ref "IC26") (pin "7") (pinfunction "GND_7") (pintype "power_in"))
      (node (ref "IC27") (pin "5") (pinfunction "I1_5") (pintype "input"))
      (node (ref "IC27") (pin "7") (pinfunction "GND_7") (pintype "power_in"))
      (node (ref "IC28") (pin "7") (pinfunction "GND_7") (pintype "power_in"))
      (node (ref "IC3") (pin "20") (pinfunction "GND_20") (pintype "power_in"))
      (node (ref "IC4") (pin "7") (pinfunction "GND_7") (pintype "power_in"))
      (node (ref "IC5") (pin "7") (pinfunction "GND_7") (pintype "power_in"))
      (node (ref "IC6") (pin "15") (pinfunction "G_15") (pintype "input"))
      (node (ref "IC6") (pin "8") (pinfunction "GND_8") (pintype "power_in"))
      (node (ref "IC7") (pin "15") (pinfunction "G_15") (pintype "input"))
      (node (ref "IC7") (pin "8") (pinfunction "GND_8") (pintype "power_in"))
      (node (ref "IC8") (pin "15") (pinfunction "G_15") (pintype "input"))
      (node (ref "IC8") (pin "8") (pinfunction "GND_8") (pintype "power_in"))
      (node (ref "IC9") (pin "15") (pinfunction "G_15") (pintype "input"))
      (node (ref "IC9") (pin "8") (pinfunction "GND_8") (pintype "power_in"))
      (node (ref "MIC") (pin "RING") (pinfunction "SHIELD_RING") (pintype "passive"))
      (node (ref "Q2") (pin "1") (pinfunction "E_1") (pintype "passive"))
      (node (ref "Q4") (pin "1") (pinfunction "E_1") (pintype "passive"))
      (node (ref "Q6") (pin "C") (pinfunction "C_C") (pintype "passive"))
      (node (ref "Q7") (pin "1") (pinfunction "E_1") (pintype "passive"))
      (node (ref "R33") (pin "2") (pinfunction "2_2") (pintype "passive"))
      (node (ref "R41") (pin "1") (pinfunction "1_1") (pintype "passive"))
      (node (ref "R47") (pin "1") (pinfunction "1_1") (pintype "passive"))
      (node (ref "R50") (pin "1") (pinfunction "1_1") (pintype "passive"))
      (node (ref "R53") (pin "2") (pinfunction "2_2") (pintype "passive"))
      (node (ref "R55") (pin "2") (pinfunction "2_2") (pintype "passive"))
      (node (ref "R60") (pin "2") (pinfunction "2_2") (pintype "passive"))
      (node (ref "R65") (pin "2") (pinfunction "2_2") (pintype "passive"))
      (node (ref "R69") (pin "1") (pinfunction "1_1") (pintype "passive"))
      (node (ref "R70") (pin "1") (pinfunction "1_1") (pintype "passive"))
      (node (ref "R73_") (pin "2") (pinfunction "2_2") (pintype "passive"))
      (node (ref "U$1") (pin "14A") (pinfunction "EDGE_14A") (pintype "bidirectional"))
      (node (ref "U$1") (pin "6A") (pinfunction "EDGE_6A") (pintype "bidirectional"))
      (node (ref "U$1") (pin "7A") (pinfunction "EDGE_7A") (pintype "bidirectional"))
      (node (ref "X2") (pin "RING") (pinfunction "SHIELD_RING") (pintype "passive"))
    )
    (net (code "75") (name "Net-(C5-Pad1)") (class "Default")
      (node (ref "C5") (pin "1") (pinfunction "1_1") (pintype "passive"))
      (node (ref "R42") (pin "1") (pinfunction "1_1") (pintype "passive"))
    )
    (net (code "76") (name "Net-(C5-Pad2)") (class "Default")
      (node (ref "C5") (pin "2") (pinfunction "2_2") (pintype "passive"))
      (node (ref "EAR") (pin "NC") (pinfunction "NC_NC") (pintype "passive"))
      (node (ref "EAR") (pin "TIP") (pinfunction "TIP_TIP") (pintype "passive"))
      (node (ref "R70") (pin "2") (pinfunction "2_2") (pintype "passive"))
    )
    (net (code "77") (name "Net-(C7-Pad1)") (class "Default")
      (node (ref "C7") (pin "1") (pinfunction "1_1") (pintype "passive"))
      (node (ref "XTAL") (pin "2") (pinfunction "2_2") (pintype "passive"))
    )
    (net (code "78") (name "Net-(C8-Pad2)") (class "Default")
      (node (ref "C8") (pin "2") (pinfunction "2_2") (pintype "passive"))
      (node (ref "Q3") (pin "B") (pinfunction "B_B") (pintype "passive"))
      (node (ref "R44") (pin "2") (pinfunction "2_2") (pintype "passive"))
      (node (ref "XTAL") (pin "1") (pinfunction "1_1") (pintype "passive"))
    )
    (net (code "79") (name "Net-(C34-Pad2)") (class "Default")
      (node (ref "C34") (pin "2") (pinfunction "2_2") (pintype "passive"))
      (node (ref "R52") (pin "2") (pinfunction "2_2") (pintype "passive"))
    )
    (net (code "80") (name "Net-(C36-Pad2)") (class "Default")
      (node (ref "C36") (pin "2") (pinfunction "2_2") (pintype "passive"))
      (node (ref "C54") (pin "2") (pinfunction "2_2") (pintype "passive"))
      (node (ref "C55") (pin "1") (pinfunction "1_1") (pintype "passive"))
      (node (ref "D25_") (pin "A") (pinfunction "A_A") (pintype "bidirectional"))
      (node (ref "R53") (pin "1") (pinfunction "1_1") (pintype "passive"))
      (node (ref "R54") (pin "2") (pinfunction "2_2") (pintype "passive"))
    )
    (net (code "81") (name "Net-(C37-Pad1)") (class "Default")
      (node (ref "C37") (pin "1") (pinfunction "1_1") (pintype "passive"))
      (node (ref "C38") (pin "2") (pinfunction "2_2") (pintype "passive"))
      (node (ref "R55") (pin "1") (pinfunction "1_1") (pintype "passive"))
    )
    (net (code "82") (name "Net-(C38-Pad1)") (class "Default")
      (node (ref "C38") (pin "1") (pinfunction "1_1") (pintype "passive"))
      (node (ref "C39") (pin "2") (pinfunction "2_2") (pintype "passive"))
      (node (ref "R56") (pin "1") (pinfunction "1_1") (pintype "passive"))
    )
    (net (code "83") (name "Net-(C39-Pad1)") (class "Default")
      (node (ref "C39") (pin "1") (pinfunction "1_1") (pintype "passive"))
      (node (ref "L2") (pin "2") (pinfunction "2_2") (pintype "passive"))
    )
    (net (code "84") (name "Net-(C49-Pad-)") (class "Default")
      (node (ref "C49") (pin "-") (pinfunction "-_-") (pintype "passive"))
      (node (ref "D19") (pin "A") (pinfunction "A_A") (pintype "bidirectional"))
      (node (ref "R67") (pin "2") (pinfunction "2_2") (pintype "passive"))
    )
    (net (code "85") (name "Net-(C56-Pad2)") (class "Default")
      (node (ref "C56") (pin "2") (pinfunction "2_2") (pintype "passive"))
      (node (ref "L2") (pin "1") (pinfunction "1_1") (pintype "passive"))
      (node (ref "R71") (pin "1") (pinfunction "1_1") (pintype "passive"))
      (node (ref "R72") (pin "2") (pinfunction "2_2") (pintype "passive"))
    )
    (net (code "86") (name "Net-(D2-PadA)") (class "Default")
      (node (ref "D2") (pin "A") (pinfunction "A_A") (pintype "bidirectional"))
      (node (ref "KB2") (pin "3") (pinfunction "3_3") (pintype "passive"))
    )
    (net (code "87") (name "Net-(D3-PadA)") (class "Default")
      (node (ref "D3") (pin "A") (pinfunction "A_A") (pintype "bidirectional"))
      (node (ref "KB2") (pin "6") (pinfunction "6_6") (pintype "passive"))
    )
    (net (code "88") (name "Net-(D4-PadA)") (class "Default")
      (node (ref "D4") (pin "A") (pinfunction "A_A") (pintype "bidirectional"))
      (node (ref "KB2") (pin "7") (pinfunction "7_7") (pintype "passive"))
    )
    (net (code "89") (name "Net-(D7-PadA)") (class "Default")
      (node (ref "D7") (pin "A") (pinfunction "A_A") (pintype "bidirectional"))
      (node (ref "KB2") (pin "4") (pinfunction "4_4") (pintype "passive"))
    )
    (net (code "90") (name "Net-(D8-PadA)") (class "Default")
      (node (ref "D8") (pin "A") (pinfunction "A_A") (pintype "bidirectional"))
      (node (ref "KB2") (pin "2") (pinfunction "2_2") (pintype "passive"))
    )
    (net (code "91") (name "Net-(D9-PadA)") (class "Default")
      (node (ref "D9") (pin "A") (pinfunction "A_A") (pintype "bidirectional"))
      (node (ref "KB2") (pin "1") (pinfunction "1_1") (pintype "passive"))
    )
    (net (code "92") (name "Net-(D11-K)") (class "Default")
      (node (ref "D11") (pin "C") (pinfunction "K_C") (pintype "bidirectional"))
      (node (ref "D12") (pin "C") (pinfunction "K_C") (pintype "bidirectional"))
      (node (ref "IC27") (pin "11") (pinfunction "O_11") (pintype "output"))
      (node (ref "R26") (pin "1") (pinfunction "1_1") (pintype "passive"))
      (node (ref "R33") (pin "1") (pinfunction "1_1") (pintype "passive"))
    )
    (net (code "93") (name "Net-(D16-K)") (class "Default")
      (node (ref "C36") (pin "1") (pinfunction "1_1") (pintype "passive"))
      (node (ref "D15") (pin "A") (pinfunction "A_A") (pintype "bidirectional"))
      (node (ref "D16") (pin "C") (pinfunction "K_C") (pintype "bidirectional"))
      (node (ref "IC3") (pin "24") (pinfunction "BEEP_24") (pintype "output"))
      (node (ref "TP7") (pin "1") (pinfunction "TP_1") (pintype "input"))
    )
    (net (code "94") (name "Net-(D19-K)") (class "Default")
      (node (ref "C48") (pin "2") (pinfunction "2_2") (pintype "passive"))
      (node (ref "D19") (pin "C") (pinfunction "K_C") (pintype "bidirectional"))
      (node (ref "D20") (pin "A") (pinfunction "A_A") (pintype "bidirectional"))
    )
    (net (code "95") (name "Net-(D22-K)") (class "Default")
      (node (ref "C51") (pin "2") (pinfunction "2_2") (pintype "passive"))
      (node (ref "D22") (pin "C") (pinfunction "K_C") (pintype "bidirectional"))
      (node (ref "D23") (pin "A") (pinfunction "A_A") (pintype "bidirectional"))
    )
    (net (code "96") (name "Net-(D23-K)") (class "Default")
      (node (ref "C52") (pin "+") (pinfunction "+_+") (pintype "passive"))
      (node (ref "D23") (pin "C") (pinfunction "K_C") (pintype "bidirectional"))
      (node (ref "R68") (pin "2") (pinfunction "2_2") (pintype "passive"))
    )
    (net (code "97") (name "Net-(D27-K)") (class "Default")
      (node (ref "D25") (pin "C") (pinfunction "C_C") (pintype "passive"))
      (node (ref "D26") (pin "C") (pinfunction "C_C") (pintype "passive"))
      (node (ref "D27") (pin "C") (pinfunction "K_C") (pintype "bidirectional"))
      (node (ref "IC3") (pin "18") (pinfunction "BRIGHT_18") (pintype "output"))
    )
    (net (code "98") (name "Net-(IC1-CLK)") (class "Default")
      (node (ref "IC1") (pin "6") (pinfunction "CLK_6") (pintype "input"))
      (node (ref "Q2") (pin "3") (pinfunction "C_3") (pintype "passive"))
      (node (ref "R48") (pin "1") (pinfunction "1_1") (pintype "passive"))
      (node (ref "TP1") (pin "1") (pinfunction "TP_1") (pintype "input"))
    )
    (net (code "99") (name "Net-(IC1-~{BUSAK})") (class "Default")
      (node (ref "IC1") (pin "23") (pinfunction "~{BUSAK}_23") (pintype "output"))
      (node (ref "U$1") (pin "26A") (pinfunction "EDGE_26A") (pintype "bidirectional"))
    )
    (net (code "100") (name "Net-(IC1-~{BUSRQ})") (class "Default")
      (node (ref "IC1") (pin "25") (pinfunction "~{BUSRQ}_25") (pintype "input"))
      (node (ref "R30") (pin "2") (pinfunction "2_2") (pintype "passive"))
      (node (ref "U$1") (pin "19A") (pinfunction "EDGE_19A") (pintype "bidirectional"))
    )
    (net (code "101") (name "Net-(IC1-~{HALT})") (class "Default")
      (node (ref "IC1") (pin "18") (pinfunction "~{HALT}_18") (pintype "output"))
      (node (ref "U$1") (pin "15B") (pinfunction "EDGE_15B") (pintype "bidirectional"))
    )
    (net (code "102") (name "Net-(IC1-~{M1})") (class "Default")
      (node (ref "IC1") (pin "27") (pinfunction "~{M1}_27") (pintype "output"))
      (node (ref "U$1") (pin "24B") (pinfunction "EDGE_24B") (pintype "bidirectional"))
    )
    (net (code "103") (name "Net-(IC1-~{NMI})") (class "Default")
      (node (ref "IC1") (pin "17") (pinfunction "~{NMI}_17") (pintype "input"))
      (node (ref "R31") (pin "2") (pinfunction "2_2") (pintype "passive"))
      (node (ref "U$1") (pin "14B") (pinfunction "EDGE_14B") (pintype "bidirectional"))
    )
    (net (code "104") (name "Net-(IC1-~{WAIT})") (class "Default")
      (node (ref "IC1") (pin "24") (pinfunction "~{WAIT}_24") (pintype "input"))
      (node (ref "R32") (pin "2") (pinfunction "2_2") (pintype "passive"))
      (node (ref "U$1") (pin "21B") (pinfunction "EDGE_21B") (pintype "bidirectional"))
    )
    (net (code "105") (name "Net-(IC3-MIC)") (class "Default")
      (node (ref "IC3") (pin "23") (pinfunction "MIC_23") (pintype "output"))
      (node (ref "R46") (pin "2") (pinfunction "2_2") (pintype "passive"))
    )
    (net (code "106") (name "Net-(IC4B-D)") (class "Default")
      (node (ref "IC4") (pin "12") (pinfunction "D_12") (pintype "input"))
      (node (ref "IC4") (pin "8") (pinfunction "~{Q}_8") (pintype "output"))
    )
    (net (code "107") (name "Net-(IC5A-CLK)") (class "Default")
      (node (ref "IC5") (pin "3") (pinfunction "CLK_3") (pintype "input"))
      (node (ref "IC5") (pin "9") (pinfunction "Q_9") (pintype "output"))
    )
    (net (code "108") (name "Net-(IC5A-D)") (class "Default")
      (node (ref "IC5") (pin "2") (pinfunction "D_2") (pintype "input"))
      (node (ref "IC5") (pin "6") (pinfunction "~{Q}_6") (pintype "output"))
    )
    (net (code "109") (name "Net-(IC8A-1Y)") (class "Default")
      (node (ref "IC8") (pin "4") (pinfunction "1Y_4") (pintype "output"))
      (node (ref "R15") (pin "2") (pinfunction "2_2") (pintype "passive"))
    )
    (net (code "110") (name "Net-(IC8A-2Y)") (class "Default")
      (node (ref "IC8") (pin "7") (pinfunction "2Y_7") (pintype "output"))
      (node (ref "R14") (pin "2") (pinfunction "2_2") (pintype "passive"))
    )
    (net (code "111") (name "Net-(IC8A-3Y)") (class "Default")
      (node (ref "IC8") (pin "9") (pinfunction "3Y_9") (pintype "output"))
      (node (ref "R12") (pin "2") (pinfunction "2_2") (pintype "passive"))
    )
    (net (code "112") (name "Net-(IC8A-4Y)") (class "Default")
      (node (ref "IC8") (pin "12") (pinfunction "4Y_12") (pintype "output"))
      (node (ref "R13") (pin "2") (pinfunction "2_2") (pintype "passive"))
    )
    (net (code "113") (name "Net-(IC8A-~{A}{slash}B)") (class "Default")
      (node (ref "IC8") (pin "1") (pinfunction "~{A}/B_1") (pintype "input"))
      (node (ref "IC9") (pin "1") (pinfunction "~{A}/B_1") (pintype "input"))
      (node (ref "R16") (pin "1") (pinfunction "1_1") (pintype "passive"))
    )
    (net (code "114") (name "Net-(IC9A-2Y)") (class "Default")
      (node (ref "IC9") (pin "7") (pinfunction "2Y_7") (pintype "output"))
      (node (ref "R11") (pin "2") (pinfunction "2_2") (pintype "passive"))
    )
    (net (code "115") (name "Net-(IC9A-3Y)") (class "Default")
      (node (ref "IC9") (pin "9") (pinfunction "3Y_9") (pintype "output"))
      (node (ref "R9") (pin "2") (pinfunction "2_2") (pintype "passive"))
    )
    (net (code "116") (name "Net-(IC9A-4Y)") (class "Default")
      (node (ref "IC9") (pin "12") (pinfunction "4Y_12") (pintype "output"))
      (node (ref "R10") (pin "2") (pinfunction "2_2") (pintype "passive"))
    )
    (net (code "117") (name "Net-(IC10A-A1)") (class "Default")
      (node (ref "IC10") (pin "2") (pinfunction "A1_2") (pintype "input"))
      (node (ref "KB1") (pin "5") (pinfunction "5_5") (pintype "passive"))
      (node (ref "P") (pin "6") (pinfunction "M_6") (pintype "passive"))
      (node (ref "R39") (pin "2") (pinfunction "2_2") (pintype "passive"))
    )
    (net (code "118") (name "Net-(IC10A-A2)") (class "Default")
      (node (ref "IC10") (pin "4") (pinfunction "A2_4") (pintype "input"))
      (node (ref "KB1") (pin "4") (pinfunction "4_4") (pintype "passive"))
      (node (ref "P") (pin "1") (pinfunction "M_1") (pintype "passive"))
      (node (ref "R38") (pin "2") (pinfunction "2_2") (pintype "passive"))
    )
    (net (code "119") (name "Net-(IC10A-A3)") (class "Default")
      (node (ref "IC10") (pin "6") (pinfunction "A3_6") (pintype "input"))
      (node (ref "KB1") (pin "3") (pinfunction "3_3") (pintype "passive"))
      (node (ref "P") (pin "2") (pinfunction "M_2") (pintype "passive"))
      (node (ref "R35") (pin "2") (pinfunction "2_2") (pintype "passive"))
    )
    (net (code "120") (name "Net-(IC10A-A4)") (class "Default")
      (node (ref "IC10") (pin "10") (pinfunction "A4_10") (pintype "input"))
      (node (ref "KB1") (pin "2") (pinfunction "2_2") (pintype "passive"))
      (node (ref "P") (pin "4") (pinfunction "M_4") (pintype "passive"))
      (node (ref "R36") (pin "2") (pinfunction "2_2") (pintype "passive"))
    )
    (net (code "121") (name "Net-(IC10A-A5)") (class "Default")
      (node (ref "IC10") (pin "12") (pinfunction "A5_12") (pintype "input"))
      (node (ref "KB1") (pin "1") (pinfunction "1_1") (pintype "passive"))
      (node (ref "P") (pin "3") (pinfunction "M_3") (pintype "passive"))
      (node (ref "R37") (pin "2") (pinfunction "2_2") (pintype "passive"))
    )
    (net (code "122") (name "Net-(IC10A-A6)") (class "Default")
      (node (ref "IC10") (pin "14") (pinfunction "A6_14") (pintype "input"))
      (node (ref "Q7") (pin "3") (pinfunction "C_3") (pintype "passive"))
      (node (ref "R74_") (pin "1") (pinfunction "1_1") (pintype "passive"))
    )
    (net (code "123") (name "Net-(IC11-B-Y)") (class "Default")
      (node (ref "C45") (pin "1") (pinfunction "1_1") (pintype "passive"))
      (node (ref "IC11") (pin "4") (pinfunction "B-Y_4") (pintype "output"))
      (node (ref "IC12") (pin "4") (pinfunction "B-Y_4") (pintype "input"))
    )
    (net (code "124") (name "Net-(IC11-B1)") (class "Default")
      (node (ref "IC11") (pin "17") (pinfunction "B3_17") (pintype "input"))
      (node (ref "IC11") (pin "19") (pinfunction "B1_19") (pintype "input"))
      (node (ref "IC3") (pin "22") (pinfunction "BLUE_22") (pintype "output"))
      (node (ref "R75") (pin "2") (pinfunction "2_2") (pintype "passive"))
    )
    (net (code "125") (name "Net-(IC11-B2)") (class "Default")
      (node (ref "D27") (pin "A") (pinfunction "A_A") (pintype "bidirectional"))
      (node (ref "IC11") (pin "18") (pinfunction "B2_18") (pintype "input"))
      (node (ref "R75") (pin "1") (pinfunction "1_1") (pintype "passive"))
    )
    (net (code "126") (name "Net-(IC11-BLANK)") (class "Default")
      (node (ref "IC11") (pin "8") (pinfunction "SYNC_8") (pintype "input"))
      (node (ref "IC11") (pin "9") (pinfunction "BLANK_9") (pintype "input"))
      (node (ref "IC3") (pin "33") (pinfunction "SYNC_33") (pintype "output"))
      (node (ref "TP8") (pin "1") (pinfunction "TP_1") (pintype "input"))
    )
    (net (code "127") (name "Net-(IC11-CREF)") (class "Default")
      (node (ref "C46") (pin "1") (pinfunction "1_1") (pintype "passive"))
      (node (ref "IC11") (pin "7") (pinfunction "CREF_7") (pintype "input"))
      (node (ref "IC12") (pin "12") (pinfunction "Y_12") (pintype "input"))
    )
    (net (code "128") (name "Net-(IC11-G1)") (class "Default")
      (node (ref "IC11") (pin "14") (pinfunction "G3_14") (pintype "input"))
      (node (ref "IC11") (pin "16") (pinfunction "G1_16") (pintype "input"))
      (node (ref "IC3") (pin "19") (pinfunction "GREEN_19") (pintype "output"))
      (node (ref "R73") (pin "2") (pinfunction "2_2") (pintype "passive"))
    )
    (net (code "129") (name "Net-(IC11-G2)") (class "Default")
      (node (ref "D25") (pin "A") (pinfunction "A_A") (pintype "passive"))
      (node (ref "IC11") (pin "15") (pinfunction "G2_15") (pintype "input"))
      (node (ref "R73") (pin "1") (pinfunction "1_1") (pintype "passive"))
    )
    (net (code "130") (name "Net-(IC11-GATE)") (class "Default")
      (node (ref "IC11") (pin "1") (pinfunction "GATE_1") (pintype "input"))
      (node (ref "IC28") (pin "6") (pinfunction "O_6") (pintype "output"))
    )
    (net (code "131") (name "Net-(IC11-H{slash}2)") (class "Default")
      (node (ref "IC11") (pin "2") (pinfunction "H/2_2") (pintype "input"))
      (node (ref "IC4") (pin "9") (pinfunction "Q_9") (pintype "output"))
    )
    (net (code "132") (name "Net-(IC11-R-Y)") (class "Default")
      (node (ref "C44") (pin "1") (pinfunction "1_1") (pintype "passive"))
      (node (ref "IC11") (pin "3") (pinfunction "R-Y_3") (pintype "output"))
      (node (ref "IC12") (pin "2") (pinfunction "R-Y_2") (pintype "input"))
    )
    (net (code "133") (name "Net-(IC11-R1)") (class "Default")
      (node (ref "IC11") (pin "11") (pinfunction "R3_11") (pintype "input"))
      (node (ref "IC11") (pin "13") (pinfunction "R1_13") (pintype "input"))
      (node (ref "IC3") (pin "21") (pinfunction "RED_21") (pintype "output"))
      (node (ref "R74") (pin "2") (pinfunction "2_2") (pintype "passive"))
    )
    (net (code "134") (name "Net-(IC11-R2)") (class "Default")
      (node (ref "D26") (pin "A") (pinfunction "A_A") (pintype "passive"))
      (node (ref "IC11") (pin "12") (pinfunction "R2_12") (pintype "input"))
      (node (ref "R74") (pin "1") (pinfunction "1_1") (pintype "passive"))
    )
    (net (code "135") (name "Net-(IC11-Y)") (class "Default")
      (node (ref "IC11") (pin "6") (pinfunction "Y_6") (pintype "output"))
      (node (ref "R63") (pin "2") (pinfunction "2_2") (pintype "passive"))
    )
    (net (code "136") (name "Net-(IC12-CHB_O)") (class "Default")
      (node (ref "C42") (pin "1") (pinfunction "1_1") (pintype "passive"))
      (node (ref "IC12") (pin "10") (pinfunction "CHB_O_10") (pintype "input"))
      (node (ref "R59") (pin "2") (pinfunction "2_2") (pintype "passive"))
    )
    (net (code "137") (name "Net-(IC12-CR_LAG)") (class "Default")
      (node (ref "C40") (pin "2") (pinfunction "2_2") (pintype "passive"))
      (node (ref "IC12") (pin "18") (pinfunction "CR_LAG_18") (pintype "output"))
      (node (ref "R56") (pin "2") (pinfunction "2_2") (pintype "passive"))
    )
    (net (code "138") (name "Net-(IC12-CR_LEAD)") (class "Default")
      (node (ref "C37") (pin "2") (pinfunction "2_2") (pintype "passive"))
      (node (ref "IC12") (pin "1") (pinfunction "CR_LEAD_1") (pintype "input"))
    )
    (net (code "139") (name "Net-(IC12-CR_OSC)") (class "Default")
      (node (ref "IC12") (pin "17") (pinfunction "CR_OSC_17") (pintype "input"))
      (node (ref "R72") (pin "1") (pinfunction "1_1") (pintype "passive"))
      (node (ref "R73_") (pin "1") (pinfunction "1_1") (pintype "passive"))
    )
    (net (code "140") (name "Net-(IC12-CR_SUBC)") (class "Default")
      (node (ref "C34") (pin "1") (pinfunction "1_1") (pintype "passive"))
      (node (ref "IC12") (pin "13") (pinfunction "CR_SUBC_13") (pintype "input"))
      (node (ref "R63") (pin "1") (pinfunction "1_1") (pintype "passive"))
    )
    (net (code "141") (name "Net-(IC12-SNDTK)") (class "Default")
      (node (ref "D25_") (pin "K") (pinfunction "K_K") (pintype "bidirectional"))
      (node (ref "IC12") (pin "15") (pinfunction "SNDTK_15") (pintype "input"))
      (node (ref "L1") (pin "4") (pinfunction "E_4") (pintype "passive"))
      (node (ref "R52") (pin "1") (pinfunction "1_1") (pintype "passive"))
    )
    (net (code "142") (name "Net-(IC12-TNKA1)") (class "Default")
      (node (ref "IC12") (pin "8") (pinfunction "TNKA1_8") (pintype "output"))
      (node (ref "IC12") (pin "9") (pinfunction "TNKA2_9") (pintype "input"))
    )
    (net (code "143") (name "Net-(IC12-TNKB1)") (class "Default")
      (node (ref "C41") (pin "2") (pinfunction "2_2") (pintype "passive"))
      (node (ref "IC12") (pin "6") (pinfunction "TNKB1_6") (pintype "output"))
      (node (ref "L3") (pin "1") (pinfunction "1_1") (pintype "passive"))
      (node (ref "R57") (pin "2") (pinfunction "2_2") (pintype "passive"))
    )
    (net (code "144") (name "Net-(IC12-TNKB2)") (class "Default")
      (node (ref "C41") (pin "1") (pinfunction "1_1") (pintype "passive"))
      (node (ref "IC12") (pin "7") (pinfunction "TNKB2_7") (pintype "input"))
      (node (ref "L3") (pin "2") (pinfunction "2_2") (pintype "passive"))
      (node (ref "R58") (pin "2") (pinfunction "2_2") (pintype "passive"))
    )
    (net (code "145") (name "Net-(IC25A-O)") (class "Default")
      (node (ref "IC25") (pin "12") (pinfunction "I0_12") (pintype "input"))
      (node (ref "IC25") (pin "3") (pinfunction "O_3") (pintype "output"))
    )
    (net (code "146") (name "Net-(IC25B-I1)") (class "Default")
      (node (ref "IC25") (pin "10") (pinfunction "I1_10") (pintype "input"))
      (node (ref "IC25") (pin "5") (pinfunction "I1_5") (pintype "input"))
      (node (ref "IC28") (pin "4") (pinfunction "O_4") (pintype "output"))
    )
    (net (code "147") (name "Net-(IC25C-I0)") (class "Default")
      (node (ref "IC25") (pin "9") (pinfunction "I0_9") (pintype "input"))
      (node (ref "IC28") (pin "2") (pinfunction "O_2") (pintype "output"))
    )
    (net (code "148") (name "Net-(IC25D-O)") (class "Default")
      (node (ref "IC25") (pin "11") (pinfunction "O_11") (pintype "output"))
      (node (ref "IC27") (pin "1") (pinfunction "I0_1") (pintype "input"))
    )
    (net (code "149") (name "Net-(IC26A-O)") (class "Default")
      (node (ref "IC26") (pin "3") (pinfunction "O_3") (pintype "output"))
      (node (ref "IC26") (pin "4") (pinfunction "I0_4") (pintype "input"))
    )
    (net (code "150") (name "Net-(IC26B-I1)") (class "Default")
      (node (ref "IC26") (pin "5") (pinfunction "I1_5") (pintype "input"))
      (node (ref "IC5") (pin "5") (pinfunction "Q_5") (pintype "output"))
    )
    (net (code "151") (name "Net-(IC26B-O)") (class "Default")
      (node (ref "IC26") (pin "6") (pinfunction "O_6") (pintype "output"))
      (node (ref "IC26") (pin "9") (pinfunction "I0_9") (pintype "input"))
    )
    (net (code "152") (name "Net-(IC26C-I1)") (class "Default")
      (node (ref "IC26") (pin "10") (pinfunction "I1_10") (pintype "input"))
      (node (ref "IC26") (pin "11") (pinfunction "O_11") (pintype "output"))
    )
    (net (code "153") (name "Net-(IC27A-I1)") (class "Default")
      (node (ref "C10") (pin "1") (pinfunction "1_1") (pintype "passive"))
      (node (ref "IC27") (pin "2") (pinfunction "I1_2") (pintype "input"))
      (node (ref "R28") (pin "2") (pinfunction "2_2") (pintype "passive"))
    )
    (net (code "154") (name "Net-(IC27C-I1)") (class "Default")
      (node (ref "C11") (pin "1") (pinfunction "1_1") (pintype "passive"))
      (node (ref "IC27") (pin "10") (pinfunction "I1_10") (pintype "input"))
      (node (ref "R45") (pin "2") (pinfunction "2_2") (pintype "passive"))
    )
    (net (code "155") (name "Net-(IC27C-O)") (class "Default")
      (node (ref "IC27") (pin "8") (pinfunction "O_8") (pintype "output"))
      (node (ref "IC28") (pin "3") (pinfunction "I_3") (pintype "input"))
    )
    (net (code "156") (name "Net-(IC28C-I)") (class "Default")
      (node (ref "IC28") (pin "5") (pinfunction "I_5") (pintype "input"))
      (node (ref "IC3") (pin "35") (pinfunction "GATE_35") (pintype "output"))
      (node (ref "IC4") (pin "11") (pinfunction "CLK_11") (pintype "input"))
    )
    (net (code "157") (name "Net-(IC28D-I)") (class "Default")
      (node (ref "C6") (pin "2") (pinfunction "2_2") (pintype "passive"))
      (node (ref "C7") (pin "2") (pinfunction "2_2") (pintype "passive"))
      (node (ref "IC28") (pin "9") (pinfunction "I_9") (pintype "input"))
      (node (ref "Q3") (pin "C") (pinfunction "C_C") (pintype "passive"))
      (node (ref "R43") (pin "1") (pinfunction "1_1") (pintype "passive"))
      (node (ref "R44") (pin "1") (pinfunction "1_1") (pintype "passive"))
    )
    (net (code "158") (name "Net-(IC28D-O)") (class "Default")
      (node (ref "IC28") (pin "11") (pinfunction "I_11") (pintype "input"))
      (node (ref "IC28") (pin "8") (pinfunction "O_8") (pintype "output"))
      (node (ref "JP") (pin "3") (pinfunction "3_3") (pintype "passive"))
    )
    (net (code "159") (name "Net-(IC28E-O)") (class "Default")
      (node (ref "IC28") (pin "10") (pinfunction "O_10") (pintype "output"))
      (node (ref "IC3") (pin "11") (pinfunction "CLK_11") (pintype "input"))
      (node (ref "JP") (pin "1") (pinfunction "1_1") (pintype "passive"))
      (node (ref "JP") (pin "2") (pinfunction "2_2") (pintype "passive"))
      (node (ref "TP2") (pin "1") (pinfunction "TP_1") (pintype "input"))
    )
    (net (code "160") (name "Net-(MIC-PadNC)") (class "Default")
      (node (ref "MIC") (pin "NC") (pinfunction "NC_NC") (pintype "passive"))
      (node (ref "MIC") (pin "TIP") (pinfunction "TIP_TIP") (pintype "passive"))
      (node (ref "R46") (pin "1") (pinfunction "1_1") (pintype "passive"))
      (node (ref "R69") (pin "2") (pinfunction "2_2") (pintype "passive"))
    )
    (net (code "161") (name "Net-(PE-M)") (class "Default")
      (node (ref "D6") (pin "A") (pinfunction "A_A") (pintype "bidirectional"))
      (node (ref "KB2") (pin "5") (pinfunction "5_5") (pintype "passive"))
      (node (ref "P") (pin "5") (pinfunction "M_5") (pintype "passive"))
      (node (ref "P") (pin "8") (pinfunction "M_8") (pintype "passive"))
      (node (ref "P") (pin "9") (pinfunction "M_9") (pintype "passive"))
    )
    (net (code "162") (name "Net-(PG-M)") (class "Default")
      (node (ref "D5") (pin "A") (pinfunction "A_A") (pintype "bidirectional"))
      (node (ref "KB2") (pin "8") (pinfunction "8_8") (pintype "passive"))
      (node (ref "P") (pin "7") (pinfunction "M_7") (pintype "passive"))
    )
    (net (code "163") (name "Net-(Q2-B)") (class "Default")
      (node (ref "C9") (pin "1") (pinfunction "1_1") (pintype "passive"))
      (node (ref "Q2") (pin "2") (pinfunction "B_2") (pintype "passive"))
      (node (ref "R49") (pin "1") (pinfunction "1_1") (pintype "passive"))
      (node (ref "R50") (pin "2") (pinfunction "2_2") (pintype "passive"))
    )
    (net (code "164") (name "Net-(Q3-PadE)") (class "Default")
      (node (ref "Q3") (pin "E") (pinfunction "E_E") (pintype "passive"))
      (node (ref "R47") (pin "2") (pinfunction "2_2") (pintype "passive"))
    )
    (net (code "165") (name "Net-(Q4-B)") (class "Default")
      (node (ref "C47") (pin "2") (pinfunction "2_2") (pintype "passive"))
      (node (ref "Q4") (pin "2") (pinfunction "B_2") (pintype "passive"))
      (node (ref "R64") (pin "1") (pinfunction "1_1") (pintype "passive"))
      (node (ref "R65") (pin "1") (pinfunction "1_1") (pintype "passive"))
    )
    (net (code "166") (name "Net-(Q4-C)") (class "Default")
      (node (ref "Q4") (pin "3") (pinfunction "C_3") (pintype "passive"))
      (node (ref "Q5") (pin "B") (pinfunction "B_B") (pintype "passive"))
      (node (ref "Q6") (pin "B") (pinfunction "B_B") (pintype "passive"))
      (node (ref "R66") (pin "2") (pinfunction "2_2") (pintype "passive"))
    )
    (net (code "167") (name "Net-(U$1Y-EDGE)") (class "Default")
      (node (ref "C55") (pin "2") (pinfunction "2_2") (pintype "passive"))
      (node (ref "U$1") (pin "4B") (pinfunction "EDGE_4B") (pintype "bidirectional"))
    )
    (net (code "168") (name "Net-(VIDEO(RF)-TP)") (class "Default")
      (node (ref "C42") (pin "2") (pinfunction "2_2") (pintype "passive"))
      (node (ref "R60") (pin "1") (pinfunction "1_1") (pintype "passive"))
      (node (ref "VIDEO(RF)") (pin "1") (pinfunction "TP_1") (pintype "input"))
    )
    (net (code "169") (name "V+") (class "Default")
      (node (ref "7805") (pin "IN") (pinfunction "IN_IN") (pintype "input"))
      (node (ref "C2") (pin "+") (pinfunction "+_+") (pintype "passive"))
      (node (ref "C23") (pin "1") (pinfunction "1_1") (pintype "passive"))
      (node (ref "C25") (pin "1") (pinfunction "1_1") (pintype "passive"))
      (node (ref "C28") (pin "1") (pinfunction "1_1") (pintype "passive"))
      (node (ref "C3") (pin "2") (pinfunction "2_2") (pintype "passive"))
      (node (ref "C30") (pin "1") (pinfunction "1_1") (pintype "passive"))
      (node (ref "D22") (pin "A") (pinfunction "A_A") (pintype "bidirectional"))
      (node (ref "IC13") (pin "8") (pinfunction "VDD_8") (pintype "power_in"))
      (node (ref "IC14") (pin "8") (pinfunction "VDD_8") (pintype "power_in"))
      (node (ref "IC15") (pin "8") (pinfunction "VDD_8") (pintype "power_in"))
      (node (ref "IC16") (pin "8") (pinfunction "VDD_8") (pintype "power_in"))
      (node (ref "IC17") (pin "8") (pinfunction "VDD_8") (pintype "power_in"))
      (node (ref "IC18") (pin "8") (pinfunction "VDD_8") (pintype "power_in"))
      (node (ref "IC19") (pin "8") (pinfunction "VDD_8") (pintype "power_in"))
      (node (ref "IC20") (pin "8") (pinfunction "VDD_8") (pintype "power_in"))
      (node (ref "Q5") (pin "C") (pinfunction "C_C") (pintype "passive"))
      (node (ref "R66") (pin "1") (pinfunction "1_1") (pintype "passive"))
      (node (ref "U$1") (pin "4A") (pinfunction "EDGE_4A") (pintype "bidirectional"))
      (node (ref "X2") (pin "TIP") (pinfunction "TIP_TIP") (pintype "passive"))
    )
    (net (code "170") (name "unconnected-(IC3-~{50}{slash}60HZ-Pad1)") (class "Default")
      (node (ref "IC3") (pin "1") (pinfunction "~{50}/60HZ_1") (pintype "input"))
    )
    (net (code "171") (name "unconnected-(IC4A-CLK-Pad3)") (class "Default")
      (node (ref "IC4") (pin "3") (pinfunction "CLK_3") (pintype "input"))
    )
    (net (code "172") (name "unconnected-(IC4A-CLR-Pad1)") (class "Default")
      (node (ref "IC4") (pin "1") (pinfunction "CLR_1") (pintype "input"))
    )
    (net (code "173") (name "unconnected-(IC4A-D-Pad2)") (class "Default")
      (node (ref "IC4") (pin "2") (pinfunction "D_2") (pintype "input"))
    )
    (net (code "174") (name "unconnected-(IC4A-PRE-Pad4)") (class "Default")
      (node (ref "IC4") (pin "4") (pinfunction "PRE_4") (pintype "input"))
    )
    (net (code "175") (name "unconnected-(IC4A-Q-Pad5)") (class "Default")
      (node (ref "IC4") (pin "5") (pinfunction "Q_5") (pintype "output"))
    )
    (net (code "176") (name "unconnected-(IC4A-~{Q}-Pad6)") (class "Default")
      (node (ref "IC4") (pin "6") (pinfunction "~{Q}_6") (pintype "output"))
    )
    (net (code "177") (name "unconnected-(IC5B-~{Q}-Pad8)") (class "Default")
      (node (ref "IC5") (pin "8") (pinfunction "~{Q}_8") (pintype "output"))
    )
    (net (code "178") (name "unconnected-(IC6A-1A-Pad2)") (class "Default")
      (node (ref "IC6") (pin "2") (pinfunction "1A_2") (pintype "input"))
    )
    (net (code "179") (name "unconnected-(IC6A-1B-Pad3)") (class "Default")
      (node (ref "IC6") (pin "3") (pinfunction "1B_3") (pintype "input"))
    )
    (net (code "180") (name "unconnected-(IC6A-1Y-Pad4)") (class "Default")
      (node (ref "IC6") (pin "4") (pinfunction "1Y_4") (pintype "output"))
    )
    (net (code "181") (name "unconnected-(IC6A-3A-Pad11)") (class "Default")
      (node (ref "IC6") (pin "11") (pinfunction "3A_11") (pintype "input"))
    )
    (net (code "182") (name "unconnected-(IC6A-3B-Pad10)") (class "Default")
      (node (ref "IC6") (pin "10") (pinfunction "3B_10") (pintype "input"))
    )
    (net (code "183") (name "unconnected-(IC6A-3Y-Pad9)") (class "Default")
      (node (ref "IC6") (pin "9") (pinfunction "3Y_9") (pintype "output"))
    )
    (net (code "184") (name "unconnected-(IC9A-1A-Pad2)") (class "Default")
      (node (ref "IC9") (pin "2") (pinfunction "1A_2") (pintype "input"))
    )
    (net (code "185") (name "unconnected-(IC9A-1B-Pad3)") (class "Default")
      (node (ref "IC9") (pin "3") (pinfunction "1B_3") (pintype "input"))
    )
    (net (code "186") (name "unconnected-(IC9A-1Y-Pad4)") (class "Default")
      (node (ref "IC9") (pin "4") (pinfunction "1Y_4") (pintype "output"))
    )
    (net (code "187") (name "unconnected-(IC12-CHA_O-Pad11)") (class "Default")
      (node (ref "IC12") (pin "11") (pinfunction "CHA_O_11") (pintype "input"))
    )
    (net (code "188") (name "unconnected-(L1B-S1-PadS2)") (class "Default")
      (node (ref "L1") (pin "S2") (pinfunction "S1_S2") (pintype "passive"))
    )
    (net (code "189") (name "unconnected-(L1B-S2-PadS1)") (class "Default")
      (node (ref "L1") (pin "S1") (pinfunction "S2_S1") (pintype "passive"))
    )
    (net (code "190") (name "unconnected-(U$1AX-EDGE-Pad28B)") (class "Default")
      (node (ref "U$1") (pin "28B") (pinfunction "EDGE_28B") (pintype "bidirectional"))
    )
    (net (code "191") (name "unconnected-(U$1F-EDGE-Pad15A)") (class "Default")
      (node (ref "U$1") (pin "15A") (pinfunction "EDGE_15A") (pintype "bidirectional"))
    )
    (net (code "192") (name "unconnected-(U$1G-EDGE-Pad16A)") (class "Default")
      (node (ref "U$1") (pin "16A") (pinfunction "EDGE_16A") (pintype "bidirectional"))
    )
    (net (code "193") (name "unconnected-(U$1H-EDGE-Pad17A)") (class "Default")
      (node (ref "U$1") (pin "17A") (pinfunction "EDGE_17A") (pintype "bidirectional"))
    )
    (net (code "194") (name "unconnected-(U$1I-EDGE-Pad18A)") (class "Default")
      (node (ref "U$1") (pin "18A") (pinfunction "EDGE_18A") (pintype "bidirectional"))
    )
    (net (code "195") (name "unconnected-(X2-PadNC)") (class "Default")
      (node (ref "X2") (pin "NC") (pinfunction "NC_NC") (pintype "passive"))
    )
  )
)
